# AMR3350_old.net
KiCad netlist of a schematic drawn in EAGLE
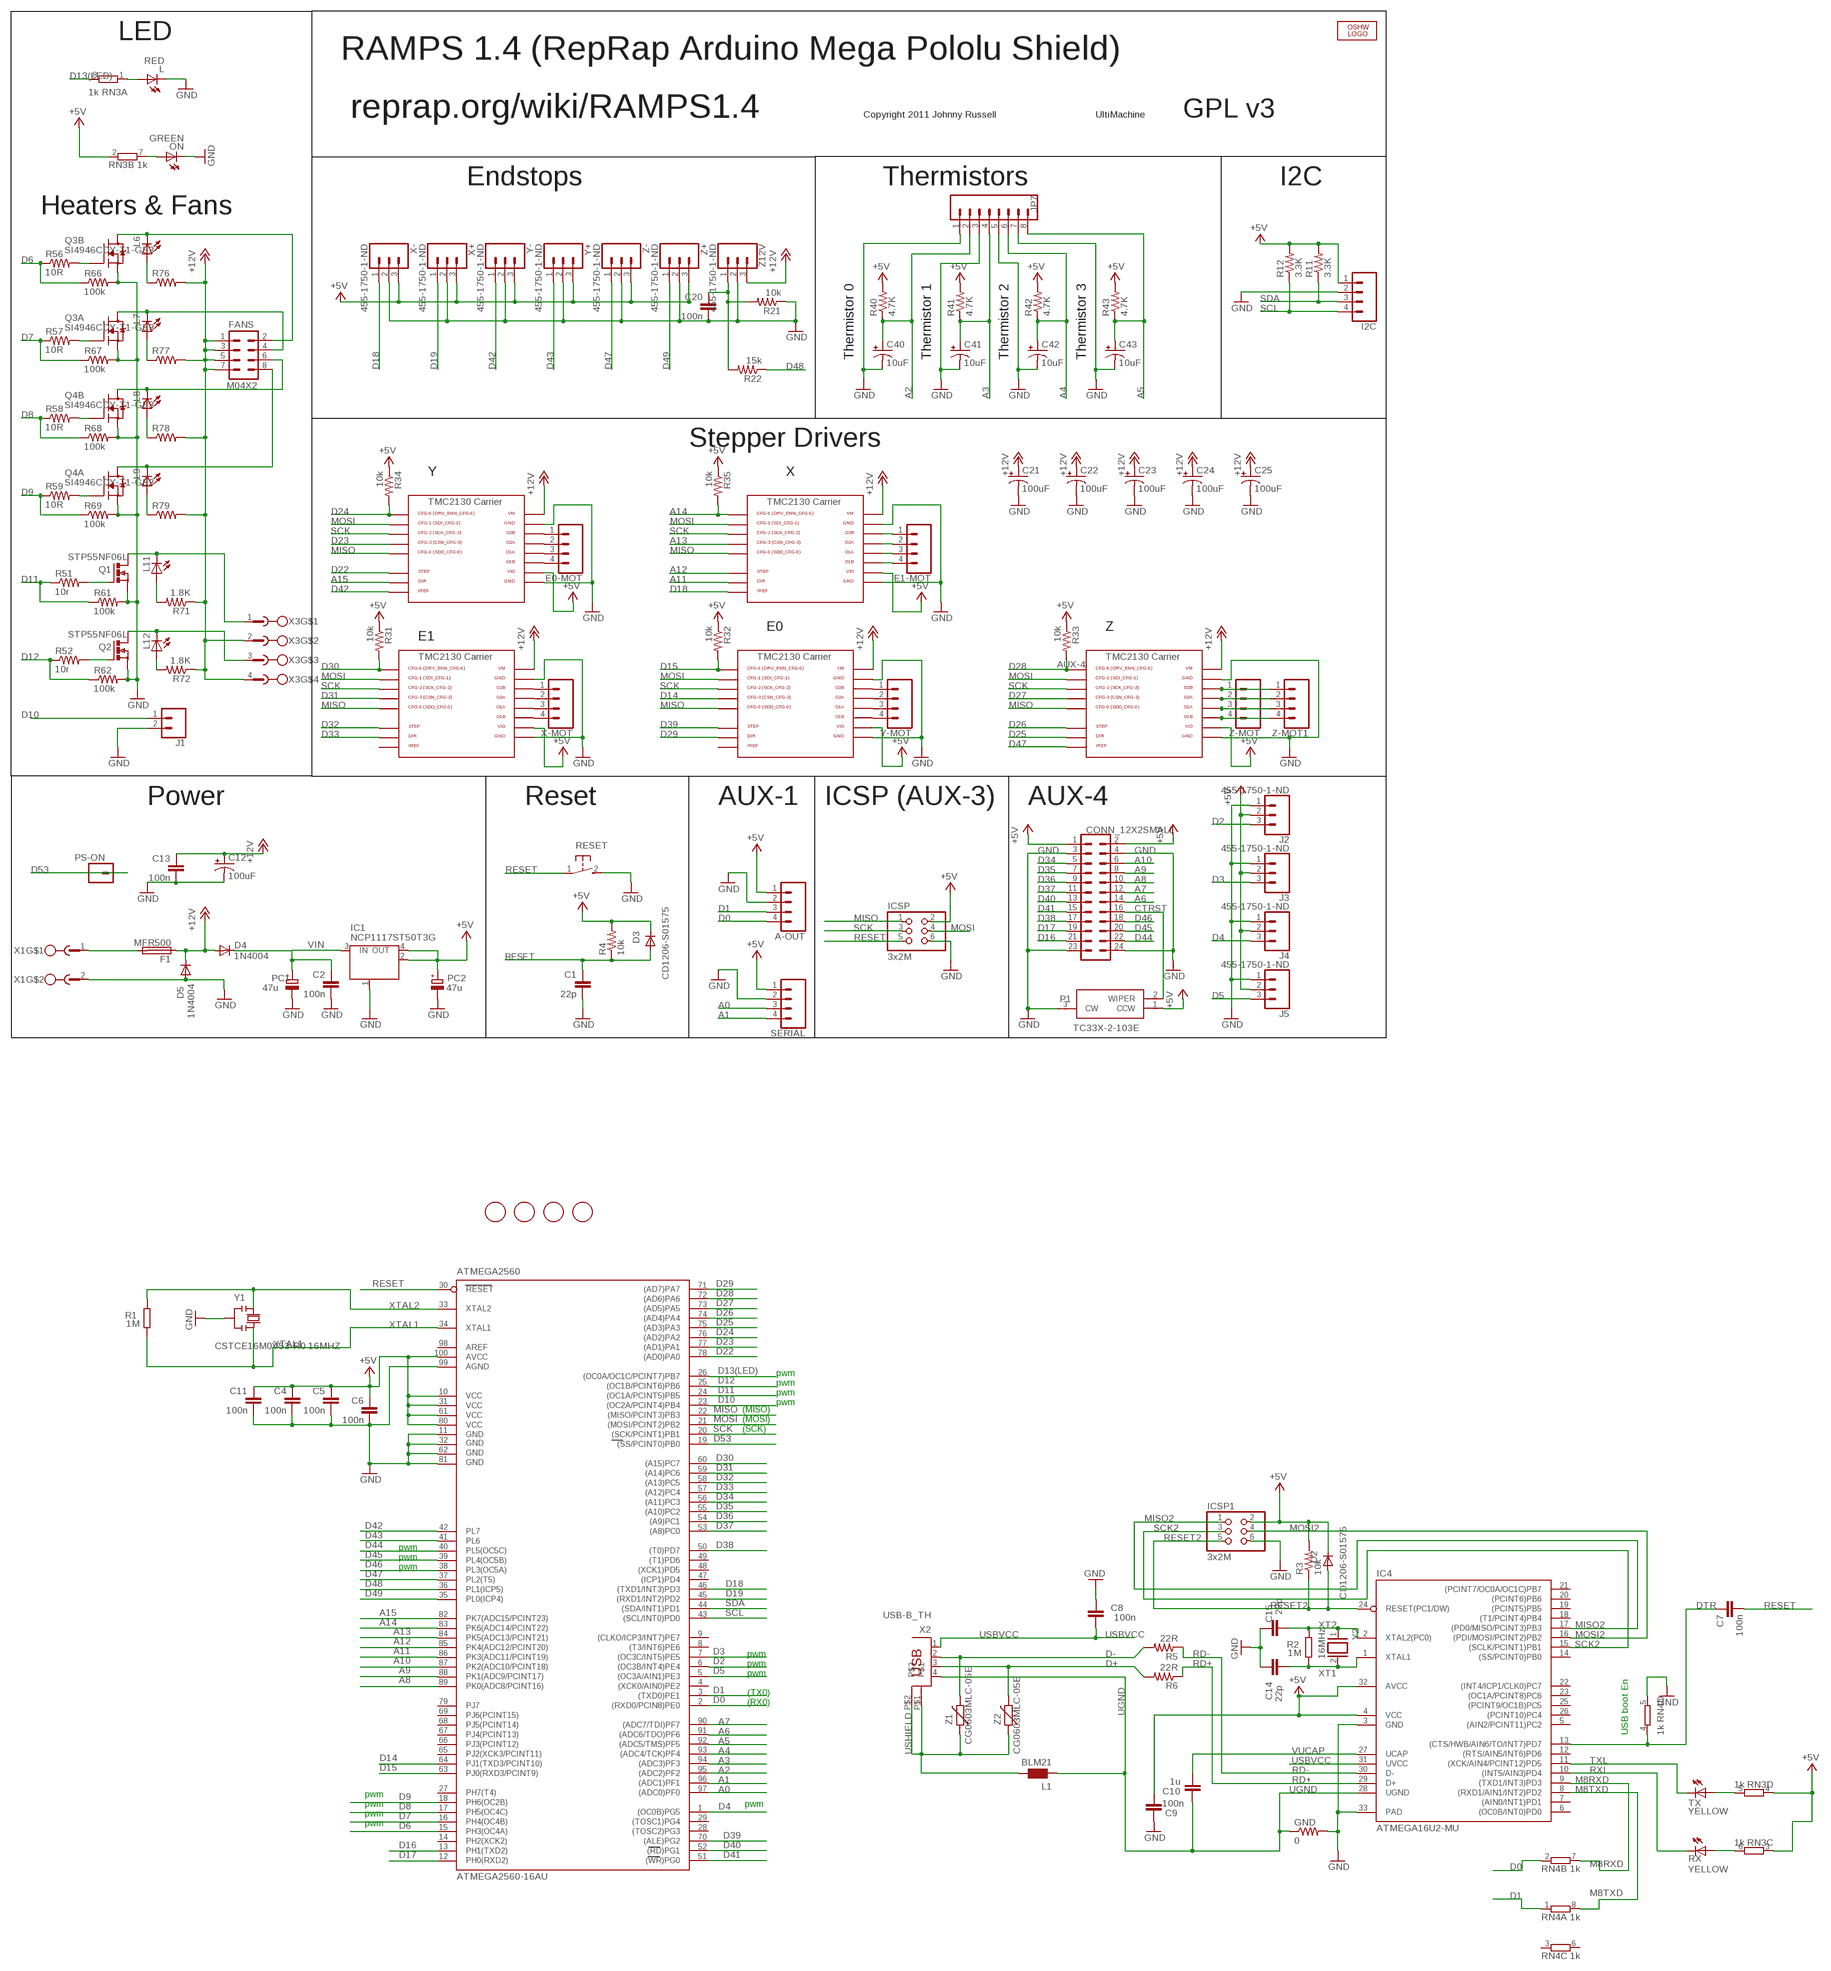
[diagram p0: schematic, sheet 1]

(export (version "E")
  (design (tool "Eeschema 10.0.6"))
  (components
    (comp (ref "A-OUT")
      (value "CONN_04SMALL")
      (footprint "eagle-import:1X04_SMALL")
      (libsource (lib "eagle-import") (part "CONN_04SMALL"))
    )
    (comp (ref "ATMEGA2560")
      (value "ATMEGA2560-16AU")
      (footprint "eagle-import:TQFP100")
      (libsource (lib "eagle-import") (part "ATMEGA2560AU2560-16"))
    )
    (comp (ref "AUX-4")
      (value "CONN_12X2SMALL")
      (footprint "eagle-import:2X12_SMALL")
      (libsource (lib "eagle-import") (part "CONN_12X2SMALL"))
    )
    (comp (ref "C1")
      (value "22p")
      (footprint "eagle-import:C0805RND")
      (libsource (lib "eagle-import") (part "C-EU"))
    )
    (comp (ref "C2")
      (value "100n")
      (footprint "eagle-import:C0805RND")
      (libsource (lib "eagle-import") (part "C-EU"))
    )
    (comp (ref "C4")
      (value "100n")
      (footprint "eagle-import:C0805RND")
      (libsource (lib "eagle-import") (part "C-EU"))
    )
    (comp (ref "C5")
      (value "100n")
      (footprint "eagle-import:C0805RND")
      (libsource (lib "eagle-import") (part "C-EU"))
    )
    (comp (ref "C6")
      (value "100n")
      (footprint "eagle-import:C0805RND")
      (libsource (lib "eagle-import") (part "C-EU"))
    )
    (comp (ref "C7")
      (value "100n")
      (footprint "eagle-import:C0805RND")
      (libsource (lib "eagle-import") (part "C-EU"))
    )
    (comp (ref "C8")
      (value "100n")
      (footprint "eagle-import:C0603-ROUND")
      (libsource (lib "eagle-import") (part "C-EU0603-RND"))
    )
    (comp (ref "C9")
      (value "100n")
      (footprint "eagle-import:C0603-ROUND")
      (libsource (lib "eagle-import") (part "C-EU0603-RND"))
    )
    (comp (ref "C10")
      (value "1u")
      (footprint "eagle-import:C0603-ROUND")
      (libsource (lib "eagle-import") (part "C-EU0603-RND"))
    )
    (comp (ref "C11")
      (value "100n")
      (footprint "eagle-import:C0603-ROUND")
      (libsource (lib "eagle-import") (part "C-EU0603-RND"))
    )
    (comp (ref "C12")
      (value "100uF")
      (footprint "eagle-import:153CLV-0605")
      (libsource (lib "eagle-import") (part "CPOL-US153CLV-0605"))
    )
    (comp (ref "C13")
      (value "100n")
      (footprint "eagle-import:C0805RND")
      (libsource (lib "eagle-import") (part "C-EU"))
    )
    (comp (ref "C14")
      (value "22p")
      (footprint "eagle-import:C0603-ROUND")
      (libsource (lib "eagle-import") (part "C-EU0603-RND"))
    )
    (comp (ref "C15")
      (value "22p")
      (footprint "eagle-import:C0603-ROUND")
      (libsource (lib "eagle-import") (part "C-EU0603-RND"))
    )
    (comp (ref "C20")
      (value "100n")
      (footprint "eagle-import:C0805RND")
      (libsource (lib "eagle-import") (part "C-EU"))
    )
    (comp (ref "C21")
      (value "100uF")
      (footprint "eagle-import:153CLV-0605")
      (libsource (lib "eagle-import") (part "CPOL-US153CLV-0605"))
    )
    (comp (ref "C22")
      (value "100uF")
      (footprint "eagle-import:153CLV-0605")
      (libsource (lib "eagle-import") (part "CPOL-US153CLV-0605"))
    )
    (comp (ref "C23")
      (value "100uF")
      (footprint "eagle-import:153CLV-0605")
      (libsource (lib "eagle-import") (part "CPOL-US153CLV-0605"))
    )
    (comp (ref "C24")
      (value "100uF")
      (footprint "eagle-import:153CLV-0605")
      (libsource (lib "eagle-import") (part "CPOL-US153CLV-0605"))
    )
    (comp (ref "C25")
      (value "100uF")
      (footprint "eagle-import:153CLV-0605")
      (libsource (lib "eagle-import") (part "CPOL-US153CLV-0605"))
    )
    (comp (ref "C40")
      (value "10uF")
      (footprint "eagle-import:153CLV-0405")
      (libsource (lib "eagle-import") (part "CPOL-US153CLV-0405"))
    )
    (comp (ref "C41")
      (value "10uF")
      (footprint "eagle-import:153CLV-0405")
      (libsource (lib "eagle-import") (part "CPOL-US153CLV-0405"))
    )
    (comp (ref "C42")
      (value "10uF")
      (footprint "eagle-import:153CLV-0405")
      (libsource (lib "eagle-import") (part "CPOL-US153CLV-0405"))
    )
    (comp (ref "C43")
      (value "10uF")
      (footprint "eagle-import:153CLV-0405")
      (libsource (lib "eagle-import") (part "CPOL-US153CLV-0405"))
    )
    (comp (ref "D2")
      (value "CD1206-S01575")
      (footprint "eagle-import:MINIMELF")
      (libsource (lib "eagle-import") (part "DIODE-MINIMELF"))
    )
    (comp (ref "D3")
      (value "CD1206-S01575")
      (footprint "eagle-import:MINIMELF")
      (libsource (lib "eagle-import") (part "DIODE-MINIMELF"))
    )
    (comp (ref "D4")
      (value "1N4004")
      (footprint "eagle-import:DO41-10")
      (libsource (lib "eagle-import") (part "1N4004"))
    )
    (comp (ref "D5")
      (value "1N4004")
      (footprint "eagle-import:DO41-10")
      (libsource (lib "eagle-import") (part "1N4004"))
    )
    (comp (ref "E0-MOT")
      (value "CONN_04SMALL")
      (footprint "eagle-import:1X04_SMALL")
      (libsource (lib "eagle-import") (part "CONN_04SMALL"))
    )
    (comp (ref "E1-MOT")
      (value "CONN_04SMALL")
      (footprint "eagle-import:1X04_SMALL")
      (libsource (lib "eagle-import") (part "CONN_04SMALL"))
    )
    (comp (ref "F1")
      (value "MFR500")
      (footprint "eagle-import:MFR500")
      (libsource (lib "eagle-import") (part "PTCFUSE"))
    )
    (comp (ref "FANS")
      (value "M04X2")
      (footprint "eagle-import:2X4")
      (libsource (lib "eagle-import") (part "M04X2"))
    )
    (comp (ref "FD1")
      (value "FIDUCIALMOUNT")
      (footprint "eagle-import:FIDUCIA-MOUNT")
      (libsource (lib "eagle-import") (part "FIDUCIALMOUNT"))
    )
    (comp (ref "FD2")
      (value "FIDUCIALMOUNT")
      (footprint "eagle-import:FIDUCIA-MOUNT")
      (libsource (lib "eagle-import") (part "FIDUCIALMOUNT"))
    )
    (comp (ref "FD3")
      (value "FIDUCIALMOUNT")
      (footprint "eagle-import:FIDUCIA-MOUNT")
      (libsource (lib "eagle-import") (part "FIDUCIALMOUNT"))
    )
    (comp (ref "FD4")
      (value "FIDUCIALMOUNT")
      (footprint "eagle-import:FIDUCIA-MOUNT")
      (libsource (lib "eagle-import") (part "FIDUCIALMOUNT"))
    )
    (comp (ref "GND")
      (value "0")
      (footprint "eagle-import:R0201")
      (libsource (lib "eagle-import") (part "R-US_R0201"))
    )
    (comp (ref "I2C")
      (value "CONN_04SMALL")
      (footprint "eagle-import:1X04_SMALL")
      (libsource (lib "eagle-import") (part "CONN_04SMALL"))
    )
    (comp (ref "IC1")
      (value "NCP1117ST50T3G")
      (footprint "eagle-import:SOT223")
      (libsource (lib "eagle-import") (part "MC33269ST-3.3T3"))
    )
    (comp (ref "IC4")
      (value "ATMEGA16U2-MU")
      (footprint "eagle-import:MLF32")
      (libsource (lib "eagle-import") (part "ATMEGA16U2-MU"))
    )
    (comp (ref "ICSP")
      (value "3x2M")
      (footprint "eagle-import:2X03")
      (libsource (lib "eagle-import") (part "PINHD-2X3"))
    )
    (comp (ref "ICSP1")
      (value "3x2M")
      (footprint "eagle-import:2X03")
      (libsource (lib "eagle-import") (part "PINHD-2X3"))
    )
    (comp (ref "J1")
      (value "CONN_02")
      (footprint "eagle-import:1X02")
      (libsource (lib "eagle-import") (part "CONN_02"))
    )
    (comp (ref "J2")
      (value "455-1750-1-ND")
      (footprint "eagle-import:1X03_SMALL")
      (libsource (lib "eagle-import") (part "CONN_03SMALL"))
    )
    (comp (ref "J3")
      (value "455-1750-1-ND")
      (footprint "eagle-import:1X03_SMALL")
      (libsource (lib "eagle-import") (part "CONN_03SMALL"))
    )
    (comp (ref "J4")
      (value "455-1750-1-ND")
      (footprint "eagle-import:1X03_SMALL")
      (libsource (lib "eagle-import") (part "CONN_03SMALL"))
    )
    (comp (ref "J5")
      (value "455-1750-1-ND")
      (footprint "eagle-import:1X03_SMALL")
      (libsource (lib "eagle-import") (part "CONN_03SMALL"))
    )
    (comp (ref "JP7")
      (value "CONN_08")
      (footprint "eagle-import:1X08_SMALL")
      (libsource (lib "eagle-import") (part "CONN_08"))
    )
    (comp (ref "L")
      (value "RED")
      (footprint "eagle-import:CHIP-LED0805")
      (libsource (lib "eagle-import") (part "LEDCHIP-LED0805"))
    )
    (comp (ref "L1")
      (value "BLM21")
      (footprint "eagle-import:0805")
      (libsource (lib "eagle-import") (part "WE-CBF_0805"))
    )
    (comp (ref "L6")
      (value "LEDCHIP-LED0603")
      (footprint "eagle-import:CHIP-LED0603")
      (libsource (lib "eagle-import") (part "LEDCHIP-LED0603"))
    )
    (comp (ref "L7")
      (value "LEDCHIP-LED0603")
      (footprint "eagle-import:CHIP-LED0603")
      (libsource (lib "eagle-import") (part "LEDCHIP-LED0603"))
    )
    (comp (ref "L8")
      (value "LEDCHIP-LED0603")
      (footprint "eagle-import:CHIP-LED0603")
      (libsource (lib "eagle-import") (part "LEDCHIP-LED0603"))
    )
    (comp (ref "L9")
      (value "LEDCHIP-LED0603")
      (footprint "eagle-import:CHIP-LED0603")
      (libsource (lib "eagle-import") (part "LEDCHIP-LED0603"))
    )
    (comp (ref "L11")
      (value "LEDCHIP-LED0805")
      (footprint "eagle-import:CHIP-LED0805")
      (libsource (lib "eagle-import") (part "LEDCHIP-LED0805"))
    )
    (comp (ref "L12")
      (value "LEDCHIP-LED0805")
      (footprint "eagle-import:CHIP-LED0805")
      (libsource (lib "eagle-import") (part "LEDCHIP-LED0805"))
    )
    (comp (ref "LOGO2")
      (value "OSHW_LOGO_6MILX0100-NT")
      (footprint "eagle-import:OSHW_6X100_NOTEXT")
      (libsource (lib "eagle-import") (part "OSHW_LOGO_6MILX0100-NT"))
    )
    (comp (ref "ON")
      (value "GREEN")
      (footprint "eagle-import:CHIP-LED0805")
      (libsource (lib "eagle-import") (part "LEDCHIP-LED0805"))
    )
    (comp (ref "P1")
      (value "TC33X-2-103E")
      (footprint "eagle-import:TC33X-2_1")
      (fields (field (name "RS_PART_NUMBER") "1673549"))
      (libsource (lib "eagle-import") (part "TC33X-2-103E"))
    )
    (comp (ref "PC1")
      (value "47u")
      (footprint "eagle-import:PANASONIC_D")
      (libsource (lib "eagle-import") (part "CPOL-EUD"))
    )
    (comp (ref "PC2")
      (value "47u")
      (footprint "eagle-import:PANASONIC_D")
      (libsource (lib "eagle-import") (part "CPOL-EUD"))
    )
    (comp (ref "PS-ON")
      (value "CONN_01SMALL")
      (footprint "eagle-import:1X01_SMALL")
      (libsource (lib "eagle-import") (part "CONN_01SMALL"))
    )
    (comp (ref "Q1")
      (value "STP55NF06L")
      (footprint "eagle-import:TO220BV")
      (libsource (lib "eagle-import") (part "IRF512"))
    )
    (comp (ref "Q2")
      (value "STP55NF06L")
      (footprint "eagle-import:TO220BV")
      (libsource (lib "eagle-import") (part "IRF512"))
    )
    (comp (ref "Q3")
      (value "SI4946CDY-T1-GE3")
      (footprint "eagle-import:SOIC127P600X175-8N")
      (libsource (lib "eagle-import") (part "SI4946CDY-T1-GE3"))
    )
    (comp (ref "Q4")
      (value "SI4946CDY-T1-GE3")
      (footprint "eagle-import:SOIC127P600X175-8N")
      (libsource (lib "eagle-import") (part "SI4946CDY-T1-GE3"))
    )
    (comp (ref "R1")
      (value "1M")
      (footprint "eagle-import:R0805RND")
      (libsource (lib "eagle-import") (part "R-EU_"))
    )
    (comp (ref "R2")
      (value "1M")
      (footprint "eagle-import:R0603-ROUND")
      (libsource (lib "eagle-import") (part "R-EU_R0603"))
    )
    (comp (ref "R3")
      (value "10k")
      (footprint "eagle-import:R0805")
      (libsource (lib "eagle-import") (part "resistor_348_R-US_R0805"))
    )
    (comp (ref "R4")
      (value "10k")
      (footprint "eagle-import:R0805")
      (libsource (lib "eagle-import") (part "resistor_348_R-US_R0805"))
    )
    (comp (ref "R5")
      (value "22R")
      (footprint "eagle-import:R0603")
      (libsource (lib "eagle-import") (part "resistor_348_R-US_R0603"))
    )
    (comp (ref "R6")
      (value "22R")
      (footprint "eagle-import:R0603")
      (libsource (lib "eagle-import") (part "resistor_348_R-US_R0603"))
    )
    (comp (ref "R11")
      (value "3.3K")
      (footprint "eagle-import:R0805")
      (libsource (lib "eagle-import") (part "R-US_R0805"))
    )
    (comp (ref "R12")
      (value "3.3K")
      (footprint "eagle-import:R0805")
      (libsource (lib "eagle-import") (part "R-US_R0805"))
    )
    (comp (ref "R21")
      (value "10k")
      (footprint "eagle-import:R0805")
      (libsource (lib "eagle-import") (part "R-US_R0805"))
    )
    (comp (ref "R22")
      (value "15k")
      (footprint "eagle-import:R0805")
      (libsource (lib "eagle-import") (part "R-US_R0805"))
    )
    (comp (ref "R31")
      (value "10k")
      (footprint "eagle-import:R0805")
      (libsource (lib "eagle-import") (part "R-US_R0805"))
    )
    (comp (ref "R32")
      (value "10k")
      (footprint "eagle-import:R0805")
      (libsource (lib "eagle-import") (part "R-US_R0805"))
    )
    (comp (ref "R33")
      (value "10k")
      (footprint "eagle-import:R0805")
      (libsource (lib "eagle-import") (part "R-US_R0805"))
    )
    (comp (ref "R34")
      (value "10k")
      (footprint "eagle-import:R0805")
      (libsource (lib "eagle-import") (part "R-US_R0805"))
    )
    (comp (ref "R35")
      (value "10k")
      (footprint "eagle-import:R0805")
      (libsource (lib "eagle-import") (part "R-US_R0805"))
    )
    (comp (ref "R40")
      (value "4.7K")
      (footprint "eagle-import:R0805")
      (libsource (lib "eagle-import") (part "R-US_R0805"))
    )
    (comp (ref "R41")
      (value "4.7K")
      (footprint "eagle-import:R0805")
      (libsource (lib "eagle-import") (part "R-US_R0805"))
    )
    (comp (ref "R42")
      (value "4.7K")
      (footprint "eagle-import:R0805")
      (libsource (lib "eagle-import") (part "R-US_R0805"))
    )
    (comp (ref "R43")
      (value "4.7K")
      (footprint "eagle-import:R0805")
      (libsource (lib "eagle-import") (part "R-US_R0805"))
    )
    (comp (ref "R51")
      (value "10r")
      (footprint "eagle-import:R0805")
      (libsource (lib "eagle-import") (part "resistor_R-US_R0805"))
    )
    (comp (ref "R52")
      (value "10r")
      (footprint "eagle-import:M0805")
      (libsource (lib "eagle-import") (part "resistor_R-US_M0805"))
    )
    (comp (ref "R56")
      (value "10R")
      (footprint "eagle-import:R0805")
      (libsource (lib "eagle-import") (part "resistor_348_R-US_R0805"))
    )
    (comp (ref "R57")
      (value "10R")
      (footprint "eagle-import:R0805")
      (libsource (lib "eagle-import") (part "resistor_348_R-US_R0805"))
    )
    (comp (ref "R58")
      (value "10R")
      (footprint "eagle-import:R0805")
      (libsource (lib "eagle-import") (part "resistor_348_R-US_R0805"))
    )
    (comp (ref "R59")
      (value "10R")
      (footprint "eagle-import:R0805")
      (libsource (lib "eagle-import") (part "resistor_348_R-US_R0805"))
    )
    (comp (ref "R61")
      (value "100k")
      (footprint "eagle-import:R0805")
      (libsource (lib "eagle-import") (part "R-US_R0805"))
    )
    (comp (ref "R62")
      (value "100k")
      (footprint "eagle-import:R0805")
      (libsource (lib "eagle-import") (part "R-US_R0805"))
    )
    (comp (ref "R66")
      (value "100k")
      (footprint "eagle-import:R0805")
      (libsource (lib "eagle-import") (part "resistor_348_R-US_R0805"))
    )
    (comp (ref "R67")
      (value "100k")
      (footprint "eagle-import:R0805")
      (libsource (lib "eagle-import") (part "resistor_348_R-US_R0805"))
    )
    (comp (ref "R68")
      (value "100k")
      (footprint "eagle-import:R0805")
      (libsource (lib "eagle-import") (part "resistor_348_R-US_R0805"))
    )
    (comp (ref "R69")
      (value "100k")
      (footprint "eagle-import:R0805")
      (libsource (lib "eagle-import") (part "resistor_348_R-US_R0805"))
    )
    (comp (ref "R71")
      (value "1.8K")
      (footprint "eagle-import:R0805")
      (libsource (lib "eagle-import") (part "R-US_R0805"))
    )
    (comp (ref "R72")
      (value "1.8K")
      (footprint "eagle-import:R0805")
      (libsource (lib "eagle-import") (part "R-US_R0805"))
    )
    (comp (ref "R76")
      (value "R-US_R0603")
      (footprint "eagle-import:R0603")
      (libsource (lib "eagle-import") (part "resistor_348_R-US_R0603"))
    )
    (comp (ref "R77")
      (value "R-US_R0603")
      (footprint "eagle-import:R0603")
      (libsource (lib "eagle-import") (part "resistor_348_R-US_R0603"))
    )
    (comp (ref "R78")
      (value "R-US_R0603")
      (footprint "eagle-import:R0603")
      (libsource (lib "eagle-import") (part "resistor_348_R-US_R0603"))
    )
    (comp (ref "R79")
      (value "R-US_R0603")
      (footprint "eagle-import:R0603")
      (libsource (lib "eagle-import") (part "resistor_348_R-US_R0603"))
    )
    (comp (ref "RESET")
      (value "31-XX")
      (footprint "eagle-import:B3F-31XX")
      (fields (field (name "MPN") "B3F-3100"))
      (libsource (lib "eagle-import") (part "31-XX"))
    )
    (comp (ref "RN3")
      (value "1k")
      (footprint "eagle-import:CAY16")
      (libsource (lib "eagle-import") (part "4R-NCAY16"))
    )
    (comp (ref "RN4")
      (value "1k")
      (footprint "eagle-import:CAY16")
      (libsource (lib "eagle-import") (part "4R-NCAY16"))
    )
    (comp (ref "RX")
      (value "YELLOW")
      (footprint "eagle-import:CHIP-LED0805")
      (libsource (lib "eagle-import") (part "LEDCHIP-LED0805"))
    )
    (comp (ref "SERIAL")
      (value "CONN_04SMALL")
      (footprint "eagle-import:1X04_SMALL")
      (libsource (lib "eagle-import") (part "CONN_04SMALL"))
    )
    (comp (ref "TX")
      (value "YELLOW")
      (footprint "eagle-import:CHIP-LED0805")
      (libsource (lib "eagle-import") (part "LEDCHIP-LED0805"))
    )
    (comp (ref "U$1")
      (value "TMC2130BREAKOUT")
      (footprint "eagle-import:TMC2130BREAKOUT")
      (libsource (lib "eagle-import") (part "TMC2130BREAKOUT"))
    )
    (comp (ref "U$2")
      (value "TMC2130BREAKOUT")
      (footprint "eagle-import:TMC2130BREAKOUT")
      (libsource (lib "eagle-import") (part "TMC2130BREAKOUT"))
    )
    (comp (ref "U$3")
      (value "TMC2130BREAKOUT")
      (footprint "eagle-import:TMC2130BREAKOUT")
      (libsource (lib "eagle-import") (part "TMC2130BREAKOUT"))
    )
    (comp (ref "U$4")
      (value "TMC2130BREAKOUT")
      (footprint "eagle-import:TMC2130BREAKOUT")
      (libsource (lib "eagle-import") (part "TMC2130BREAKOUT"))
    )
    (comp (ref "U$5")
      (value "TMC2130BREAKOUT")
      (footprint "eagle-import:TMC2130BREAKOUT")
      (libsource (lib "eagle-import") (part "TMC2130BREAKOUT"))
    )
    (comp (ref "X+")
      (value "455-1750-1-ND")
      (footprint "eagle-import:1X03_SMALL")
      (libsource (lib "eagle-import") (part "CONN_03SMALL"))
    )
    (comp (ref "X-")
      (value "455-1750-1-ND")
      (footprint "eagle-import:1X03_SMALL")
      (libsource (lib "eagle-import") (part "CONN_03SMALL"))
    )
    (comp (ref "X-MOT")
      (value "CONN_04SMALL")
      (footprint "eagle-import:1X04_SMALL")
      (libsource (lib "eagle-import") (part "CONN_04SMALL"))
    )
    (comp (ref "X1")
      (value "2-PIN")
      (footprint "eagle-import:2-PIN")
      (libsource (lib "eagle-import") (part "2-PIN"))
    )
    (comp (ref "X2")
      (value "USB-B_TH")
      (footprint "eagle-import:PN61729-NOSILK")
      (libsource (lib "eagle-import") (part "PN61729NOSILK"))
    )
    (comp (ref "X3")
      (value "4-PIN")
      (footprint "eagle-import:4-PIN")
      (libsource (lib "eagle-import") (part "4-PIN"))
    )
    (comp (ref "Y+")
      (value "455-1750-1-ND")
      (footprint "eagle-import:1X03_SMALL")
      (libsource (lib "eagle-import") (part "CONN_03SMALL"))
    )
    (comp (ref "Y-")
      (value "455-1750-1-ND")
      (footprint "eagle-import:1X03_SMALL")
      (libsource (lib "eagle-import") (part "CONN_03SMALL"))
    )
    (comp (ref "Y-MOT")
      (value "CONN_04SMALL")
      (footprint "eagle-import:1X04_SMALL")
      (libsource (lib "eagle-import") (part "CONN_04SMALL"))
    )
    (comp (ref "Y1")
      (value "CSTCE16M0V53-R0 16MHZ")
      (footprint "eagle-import:RESONATOR")
      (libsource (lib "eagle-import") (part "RESONATORMU"))
    )
    (comp (ref "Y2")
      (value "16MHz")
      (footprint "eagle-import:QS")
      (libsource (lib "eagle-import") (part "XTAL/S"))
    )
    (comp (ref "Z+")
      (value "455-1750-1-ND")
      (footprint "eagle-import:1X03_SMALL")
      (libsource (lib "eagle-import") (part "CONN_03SMALL"))
    )
    (comp (ref "Z-")
      (value "455-1750-1-ND")
      (footprint "eagle-import:1X03_SMALL")
      (libsource (lib "eagle-import") (part "CONN_03SMALL"))
    )
    (comp (ref "Z-MOT")
      (value "CONN_04SMALL")
      (footprint "eagle-import:1X04_SMALL")
      (libsource (lib "eagle-import") (part "CONN_04SMALL"))
    )
    (comp (ref "Z-MOT1")
      (value "CONN_04SMALL")
      (footprint "eagle-import:1X04_SMALL")
      (libsource (lib "eagle-import") (part "CONN_04SMALL"))
    )
    (comp (ref "Z1")
      (value "CG0603MLC-05E")
      (footprint "eagle-import:CT_CN0603")
      (libsource (lib "eagle-import") (part "VARISTORCN0603"))
    )
    (comp (ref "Z2")
      (value "CG0603MLC-05E")
      (footprint "eagle-import:CT_CN0603")
      (libsource (lib "eagle-import") (part "VARISTORCN0603"))
    )
    (comp (ref "Z12V")
      (value "455-1750-1-ND")
      (footprint "eagle-import:1X03_SMALL")
      (libsource (lib "eagle-import") (part "CONN_03SMALL"))
    )
  )
  (nets
    (net (code "1") (name "+5V") (class "Default")
      (node (ref "A-OUT") (pin "1") (pinfunction "1_1") (pintype "passive"))
      (node (ref "ATMEGA2560") (pin "10") (pinfunction "VCC_10") (pintype "power_in"))
      (node (ref "ATMEGA2560") (pin "100") (pinfunction "AVCC_100") (pintype "power_in"))
      (node (ref "ATMEGA2560") (pin "31") (pinfunction "VCC1_31") (pintype "power_in"))
      (node (ref "ATMEGA2560") (pin "61") (pinfunction "VCC2_61") (pintype "power_in"))
      (node (ref "ATMEGA2560") (pin "80") (pinfunction "VCC3_80") (pintype "power_in"))
      (node (ref "AUX-4") (pin "1") (pinfunction "1_1") (pintype "passive"))
      (node (ref "AUX-4") (pin "2") (pinfunction "2_2") (pintype "passive"))
      (node (ref "C11") (pin "1") (pinfunction "1_1") (pintype "passive"))
      (node (ref "C4") (pin "1") (pinfunction "1_1") (pintype "passive"))
      (node (ref "C5") (pin "1") (pinfunction "1_1") (pintype "passive"))
      (node (ref "C6") (pin "1") (pinfunction "1_1") (pintype "passive"))
      (node (ref "C9") (pin "1") (pinfunction "1_1") (pintype "passive"))
      (node (ref "D2") (pin "C") (pinfunction "C_C") (pintype "passive"))
      (node (ref "D3") (pin "C") (pinfunction "C_C") (pintype "passive"))
      (node (ref "I2C") (pin "1") (pinfunction "1_1") (pintype "passive"))
      (node (ref "IC1") (pin "2") (pinfunction "OUT_2") (pintype "passive"))
      (node (ref "IC1") (pin "4") (pinfunction "OUT_4") (pintype "passive"))
      (node (ref "IC4") (pin "32") (pinfunction "AVCC_32") (pintype "power_in"))
      (node (ref "IC4") (pin "4") (pinfunction "VCC_4") (pintype "power_in"))
      (node (ref "ICSP") (pin "2") (pinfunction "2_2") (pintype "passive"))
      (node (ref "ICSP1") (pin "2") (pinfunction "2_2") (pintype "passive"))
      (node (ref "J2") (pin "2") (pinfunction "2_2") (pintype "passive"))
      (node (ref "J3") (pin "2") (pinfunction "2_2") (pintype "passive"))
      (node (ref "J4") (pin "2") (pinfunction "2_2") (pintype "passive"))
      (node (ref "J5") (pin "2") (pinfunction "2_2") (pintype "passive"))
      (node (ref "P1") (pin "1") (pinfunction "CCW_1") (pintype "bidirectional"))
      (node (ref "PC2") (pin "+") (pinfunction "+_+") (pintype "passive"))
      (node (ref "R11") (pin "2") (pinfunction "2_2") (pintype "passive"))
      (node (ref "R12") (pin "2") (pinfunction "2_2") (pintype "passive"))
      (node (ref "R3") (pin "2") (pinfunction "2_2") (pintype "passive"))
      (node (ref "R31") (pin "1") (pinfunction "1_1") (pintype "passive"))
      (node (ref "R32") (pin "1") (pinfunction "1_1") (pintype "passive"))
      (node (ref "R33") (pin "1") (pinfunction "1_1") (pintype "passive"))
      (node (ref "R34") (pin "1") (pinfunction "1_1") (pintype "passive"))
      (node (ref "R35") (pin "1") (pinfunction "1_1") (pintype "passive"))
      (node (ref "R4") (pin "2") (pinfunction "2_2") (pintype "passive"))
      (node (ref "R40") (pin "2") (pinfunction "2_2") (pintype "passive"))
      (node (ref "R41") (pin "2") (pinfunction "2_2") (pintype "passive"))
      (node (ref "R42") (pin "2") (pinfunction "2_2") (pintype "passive"))
      (node (ref "R43") (pin "2") (pinfunction "2_2") (pintype "passive"))
      (node (ref "RN3") (pin "2") (pinfunction "1_2") (pintype "passive"))
      (node (ref "RN3") (pin "3") (pinfunction "1_3") (pintype "passive"))
      (node (ref "RN3") (pin "4") (pinfunction "1_4") (pintype "passive"))
      (node (ref "SERIAL") (pin "1") (pinfunction "1_1") (pintype "passive"))
      (node (ref "U$1") (pin "VIO") (pinfunction "VIO_VIO") (pintype "power_in"))
      (node (ref "U$2") (pin "VIO") (pinfunction "VIO_VIO") (pintype "power_in"))
      (node (ref "U$3") (pin "VIO") (pinfunction "VIO_VIO") (pintype "power_in"))
      (node (ref "U$4") (pin "VIO") (pinfunction "VIO_VIO") (pintype "power_in"))
      (node (ref "U$5") (pin "VIO") (pinfunction "VIO_VIO") (pintype "power_in"))
      (node (ref "X+") (pin "3") (pinfunction "3_3") (pintype "passive"))
      (node (ref "X-") (pin "3") (pinfunction "3_3") (pintype "passive"))
      (node (ref "Y+") (pin "3") (pinfunction "3_3") (pintype "passive"))
      (node (ref "Y-") (pin "3") (pinfunction "3_3") (pintype "passive"))
      (node (ref "Z+") (pin "3") (pinfunction "3_3") (pintype "passive"))
      (node (ref "Z-") (pin "3") (pinfunction "3_3") (pintype "passive"))
    )
    (net (code "2") (name "+12V") (class "Default")
      (node (ref "C12") (pin "+") (pinfunction "+_+") (pintype "passive"))
      (node (ref "C13") (pin "1") (pinfunction "1_1") (pintype "passive"))
      (node (ref "C21") (pin "+") (pinfunction "+_+") (pintype "passive"))
      (node (ref "C22") (pin "+") (pinfunction "+_+") (pintype "passive"))
      (node (ref "C23") (pin "+") (pinfunction "+_+") (pintype "passive"))
      (node (ref "C24") (pin "+") (pinfunction "+_+") (pintype "passive"))
      (node (ref "C25") (pin "+") (pinfunction "+_+") (pintype "passive"))
      (node (ref "D4") (pin "A") (pinfunction "A_A") (pintype "passive"))
      (node (ref "D5") (pin "C") (pinfunction "C_C") (pintype "passive"))
      (node (ref "F1") (pin "1") (pinfunction "1_1") (pintype "passive"))
      (node (ref "FANS") (pin "1") (pinfunction "1_1") (pintype "passive"))
      (node (ref "FANS") (pin "3") (pinfunction "3_3") (pintype "passive"))
      (node (ref "FANS") (pin "5") (pinfunction "5_5") (pintype "passive"))
      (node (ref "FANS") (pin "7") (pinfunction "7_7") (pintype "passive"))
      (node (ref "R71") (pin "1") (pinfunction "1_1") (pintype "passive"))
      (node (ref "R72") (pin "1") (pinfunction "1_1") (pintype "passive"))
      (node (ref "R76") (pin "2") (pinfunction "2_2") (pintype "passive"))
      (node (ref "R77") (pin "2") (pinfunction "2_2") (pintype "passive"))
      (node (ref "R78") (pin "2") (pinfunction "2_2") (pintype "passive"))
      (node (ref "R79") (pin "2") (pinfunction "2_2") (pintype "passive"))
      (node (ref "U$1") (pin "VM") (pinfunction "VM_VM") (pintype "power_in"))
      (node (ref "U$2") (pin "VM") (pinfunction "VM_VM") (pintype "power_in"))
      (node (ref "U$3") (pin "VM") (pinfunction "VM_VM") (pintype "power_in"))
      (node (ref "U$4") (pin "VM") (pinfunction "VM_VM") (pintype "power_in"))
      (node (ref "U$5") (pin "VM") (pinfunction "VM_VM") (pintype "power_in"))
      (node (ref "X3") (pin "2") (pinfunction "1_2") (pintype "passive"))
      (node (ref "X3") (pin "4") (pinfunction "1_4") (pintype "passive"))
      (node (ref "Z12V") (pin "3") (pinfunction "3_3") (pintype "passive"))
    )
    (net (code "3") (name "/A0") (class "Default")
      (node (ref "ATMEGA2560") (pin "97") (pinfunction "(ADC0)PF0_97") (pintype "bidirectional"))
      (node (ref "SERIAL") (pin "3") (pinfunction "3_3") (pintype "passive"))
    )
    (net (code "4") (name "/A1") (class "Default")
      (node (ref "ATMEGA2560") (pin "96") (pinfunction "(ADC1)PF1_96") (pintype "bidirectional"))
      (node (ref "SERIAL") (pin "4") (pinfunction "4_4") (pintype "passive"))
    )
    (net (code "5") (name "/A2") (class "Default")
      (node (ref "ATMEGA2560") (pin "95") (pinfunction "(ADC2)PF2_95") (pintype "bidirectional"))
      (node (ref "C40") (pin "+") (pinfunction "+_+") (pintype "passive"))
      (node (ref "JP7") (pin "2") (pinfunction "2_2") (pintype "passive"))
      (node (ref "R40") (pin "1") (pinfunction "1_1") (pintype "passive"))
    )
    (net (code "6") (name "/A3") (class "Default")
      (node (ref "ATMEGA2560") (pin "94") (pinfunction "(ADC3)PF3_94") (pintype "bidirectional"))
      (node (ref "C41") (pin "+") (pinfunction "+_+") (pintype "passive"))
      (node (ref "JP7") (pin "4") (pinfunction "4_4") (pintype "passive"))
      (node (ref "R41") (pin "1") (pinfunction "1_1") (pintype "passive"))
    )
    (net (code "7") (name "/A4") (class "Default")
      (node (ref "ATMEGA2560") (pin "93") (pinfunction "(ADC4/TCK)PF4_93") (pintype "bidirectional"))
      (node (ref "C42") (pin "+") (pinfunction "+_+") (pintype "passive"))
      (node (ref "JP7") (pin "6") (pinfunction "6_6") (pintype "passive"))
      (node (ref "R42") (pin "1") (pinfunction "1_1") (pintype "passive"))
    )
    (net (code "8") (name "/A5") (class "Default")
      (node (ref "ATMEGA2560") (pin "92") (pinfunction "(ADC5/TMS)PF5_92") (pintype "bidirectional"))
      (node (ref "C43") (pin "+") (pinfunction "+_+") (pintype "passive"))
      (node (ref "JP7") (pin "8") (pinfunction "8_8") (pintype "passive"))
      (node (ref "R43") (pin "1") (pinfunction "1_1") (pintype "passive"))
    )
    (net (code "9") (name "/A6") (class "Default")
      (node (ref "ATMEGA2560") (pin "91") (pinfunction "(ADC6/TDO)PF6_91") (pintype "bidirectional"))
      (node (ref "AUX-4") (pin "14") (pinfunction "14_14") (pintype "passive"))
    )
    (net (code "10") (name "/A7") (class "Default")
      (node (ref "ATMEGA2560") (pin "90") (pinfunction "(ADC7/TDI)PF7_90") (pintype "bidirectional"))
      (node (ref "AUX-4") (pin "12") (pinfunction "12_12") (pintype "passive"))
    )
    (net (code "11") (name "/A8") (class "Default")
      (node (ref "ATMEGA2560") (pin "89") (pinfunction "PK0(ADC8/PCINT16)_89") (pintype "bidirectional"))
      (node (ref "AUX-4") (pin "10") (pinfunction "10_10") (pintype "passive"))
    )
    (net (code "12") (name "/A9") (class "Default")
      (node (ref "ATMEGA2560") (pin "88") (pinfunction "PK1(ADC9/PCINT17)_88") (pintype "bidirectional"))
      (node (ref "AUX-4") (pin "8") (pinfunction "8_8") (pintype "passive"))
    )
    (net (code "13") (name "/A10") (class "Default")
      (node (ref "ATMEGA2560") (pin "87") (pinfunction "PK2(ADC10/PCINT18)_87") (pintype "bidirectional"))
      (node (ref "AUX-4") (pin "6") (pinfunction "6_6") (pintype "passive"))
    )
    (net (code "14") (name "/A11") (class "Default")
      (node (ref "ATMEGA2560") (pin "86") (pinfunction "PK3(ADC11/PCINT19)_86") (pintype "bidirectional"))
      (node (ref "U$4") (pin "DIR") (pinfunction "DIR_DIR") (pintype "input"))
    )
    (net (code "15") (name "/A12") (class "Default")
      (node (ref "ATMEGA2560") (pin "85") (pinfunction "PK4(ADC12/PCINT20)_85") (pintype "bidirectional"))
      (node (ref "U$4") (pin "STEP") (pinfunction "STEP_STEP") (pintype "input"))
    )
    (net (code "16") (name "/A13") (class "Default")
      (node (ref "ATMEGA2560") (pin "84") (pinfunction "PK5(ADC13/PCINT21)_84") (pintype "bidirectional"))
      (node (ref "U$4") (pin "CFG-3") (pinfunction "CFG-3_CFG-3") (pintype "bidirectional"))
    )
    (net (code "17") (name "/A14") (class "Default")
      (node (ref "ATMEGA2560") (pin "83") (pinfunction "PK6(ADC14/PCINT22)_83") (pintype "bidirectional"))
      (node (ref "R35") (pin "2") (pinfunction "2_2") (pintype "passive"))
      (node (ref "U$4") (pin "CFG-6") (pinfunction "CFG-6_CFG-6") (pintype "bidirectional"))
    )
    (net (code "18") (name "/A15") (class "Default")
      (node (ref "ATMEGA2560") (pin "82") (pinfunction "PK7(ADC15/PCINT23)_82") (pintype "bidirectional"))
      (node (ref "U$5") (pin "DIR") (pinfunction "DIR_DIR") (pintype "input"))
    )
    (net (code "19") (name "/CTRST") (class "Default")
      (node (ref "AUX-4") (pin "16") (pinfunction "16_16") (pintype "passive"))
      (node (ref "P1") (pin "2") (pinfunction "WIPER_2") (pintype "bidirectional"))
    )
    (net (code "20") (name "/D+") (class "Default")
      (node (ref "R6") (pin "2") (pinfunction "2_2") (pintype "passive"))
      (node (ref "X2") (pin "3") (pinfunction "3_3") (pintype "bidirectional"))
      (node (ref "Z2") (pin "2") (pinfunction "2_2") (pintype "passive"))
    )
    (net (code "21") (name "/D-") (class "Default")
      (node (ref "R5") (pin "2") (pinfunction "2_2") (pintype "passive"))
      (node (ref "X2") (pin "2") (pinfunction "2_2") (pintype "bidirectional"))
      (node (ref "Z1") (pin "2") (pinfunction "2_2") (pintype "passive"))
    )
    (net (code "22") (name "/D0") (class "Default")
      (node (ref "A-OUT") (pin "4") (pinfunction "4_4") (pintype "passive"))
      (node (ref "ATMEGA2560") (pin "2") (pinfunction "(RXD0/PCIN8)PE0_2") (pintype "bidirectional"))
      (node (ref "RN4") (pin "2") (pinfunction "1_2") (pintype "passive"))
    )
    (net (code "23") (name "/D1") (class "Default")
      (node (ref "A-OUT") (pin "3") (pinfunction "3_3") (pintype "passive"))
      (node (ref "ATMEGA2560") (pin "3") (pinfunction "(TXD0)PE1_3") (pintype "bidirectional"))
      (node (ref "RN4") (pin "1") (pinfunction "1_1") (pintype "passive"))
    )
    (net (code "24") (name "/D2") (class "Default")
      (node (ref "ATMEGA2560") (pin "6") (pinfunction "(OC3B/INT4)PE4_6") (pintype "bidirectional"))
      (node (ref "J2") (pin "3") (pinfunction "3_3") (pintype "passive"))
    )
    (net (code "25") (name "/D3") (class "Default")
      (node (ref "ATMEGA2560") (pin "7") (pinfunction "(OC3C/INT5)PE5_7") (pintype "bidirectional"))
      (node (ref "J3") (pin "3") (pinfunction "3_3") (pintype "passive"))
    )
    (net (code "26") (name "/D4") (class "Default")
      (node (ref "ATMEGA2560") (pin "1") (pinfunction "(OC0B)PG5_1") (pintype "bidirectional"))
      (node (ref "J4") (pin "3") (pinfunction "3_3") (pintype "passive"))
    )
    (net (code "27") (name "/D5") (class "Default")
      (node (ref "ATMEGA2560") (pin "5") (pinfunction "(OC3A/AIN1)PE3_5") (pintype "bidirectional"))
      (node (ref "J5") (pin "3") (pinfunction "3_3") (pintype "passive"))
    )
    (net (code "28") (name "/D6") (class "Default")
      (node (ref "ATMEGA2560") (pin "15") (pinfunction "PH3(OC4A)_15") (pintype "bidirectional"))
      (node (ref "R56") (pin "1") (pinfunction "1_1") (pintype "passive"))
      (node (ref "R66") (pin "1") (pinfunction "1_1") (pintype "passive"))
    )
    (net (code "29") (name "/D7") (class "Default")
      (node (ref "ATMEGA2560") (pin "16") (pinfunction "PH4(OC4B)_16") (pintype "bidirectional"))
      (node (ref "R57") (pin "1") (pinfunction "1_1") (pintype "passive"))
      (node (ref "R67") (pin "1") (pinfunction "1_1") (pintype "passive"))
    )
    (net (code "30") (name "/D8") (class "Default")
      (node (ref "ATMEGA2560") (pin "17") (pinfunction "PH5(OC4C)_17") (pintype "bidirectional"))
      (node (ref "R58") (pin "1") (pinfunction "1_1") (pintype "passive"))
      (node (ref "R68") (pin "1") (pinfunction "1_1") (pintype "passive"))
    )
    (net (code "31") (name "/D9") (class "Default")
      (node (ref "ATMEGA2560") (pin "18") (pinfunction "PH6(OC2B)_18") (pintype "bidirectional"))
      (node (ref "R59") (pin "1") (pinfunction "1_1") (pintype "passive"))
      (node (ref "R69") (pin "1") (pinfunction "1_1") (pintype "passive"))
    )
    (net (code "32") (name "/D10") (class "Default")
      (node (ref "ATMEGA2560") (pin "23") (pinfunction "(OC2A/PCINT4)PB4_23") (pintype "bidirectional"))
      (node (ref "J1") (pin "1") (pinfunction "1_1") (pintype "passive"))
    )
    (net (code "33") (name "/D11") (class "Default")
      (node (ref "ATMEGA2560") (pin "24") (pinfunction "(OC1A/PCINT5)PB5_24") (pintype "bidirectional"))
      (node (ref "R51") (pin "1") (pinfunction "1_1") (pintype "passive"))
      (node (ref "R61") (pin "1") (pinfunction "1_1") (pintype "passive"))
    )
    (net (code "34") (name "/D12") (class "Default")
      (node (ref "ATMEGA2560") (pin "25") (pinfunction "(OC1B/PCINT6)PB6_25") (pintype "bidirectional"))
      (node (ref "R52") (pin "1") (pinfunction "1_1") (pintype "passive"))
      (node (ref "R62") (pin "1") (pinfunction "1_1") (pintype "passive"))
    )
    (net (code "35") (name "/D13(LED)") (class "Default")
      (node (ref "ATMEGA2560") (pin "26") (pinfunction "(OC0A/OC1C/PCINT7)PB7_26") (pintype "bidirectional"))
      (node (ref "RN3") (pin "8") (pinfunction "2_8") (pintype "passive"))
    )
    (net (code "36") (name "/D14") (class "Default")
      (node (ref "ATMEGA2560") (pin "64") (pinfunction "PJ1(TXD3/PCINT10)_64") (pintype "bidirectional"))
      (node (ref "U$2") (pin "CFG-3") (pinfunction "CFG-3_CFG-3") (pintype "bidirectional"))
    )
    (net (code "37") (name "/D15") (class "Default")
      (node (ref "ATMEGA2560") (pin "63") (pinfunction "PJ0(RXD3/PCINT9)_63") (pintype "bidirectional"))
      (node (ref "R32") (pin "2") (pinfunction "2_2") (pintype "passive"))
      (node (ref "U$2") (pin "CFG-6") (pinfunction "CFG-6_CFG-6") (pintype "bidirectional"))
    )
    (net (code "38") (name "/D16") (class "Default")
      (node (ref "ATMEGA2560") (pin "13") (pinfunction "PH1(TXD2)_13") (pintype "bidirectional"))
      (node (ref "AUX-4") (pin "21") (pinfunction "21_21") (pintype "passive"))
    )
    (net (code "39") (name "/D17") (class "Default")
      (node (ref "ATMEGA2560") (pin "12") (pinfunction "PH0(RXD2)_12") (pintype "bidirectional"))
      (node (ref "AUX-4") (pin "19") (pinfunction "19_19") (pintype "passive"))
    )
    (net (code "40") (name "/D18") (class "Default")
      (node (ref "ATMEGA2560") (pin "46") (pinfunction "(TXD1/INT3)PD3_46") (pintype "bidirectional"))
      (node (ref "U$4") (pin "IREF") (pinfunction "IREF_IREF") (pintype "bidirectional"))
      (node (ref "X-") (pin "1") (pinfunction "1_1") (pintype "passive"))
    )
    (net (code "41") (name "/D19") (class "Default")
      (node (ref "ATMEGA2560") (pin "45") (pinfunction "(RXD1/INT2)PD2_45") (pintype "bidirectional"))
      (node (ref "X+") (pin "1") (pinfunction "1_1") (pintype "passive"))
    )
    (net (code "42") (name "/D22") (class "Default")
      (node (ref "ATMEGA2560") (pin "78") (pinfunction "(AD0)PA0_78") (pintype "bidirectional"))
      (node (ref "U$5") (pin "STEP") (pinfunction "STEP_STEP") (pintype "input"))
    )
    (net (code "43") (name "/D23") (class "Default")
      (node (ref "ATMEGA2560") (pin "77") (pinfunction "(AD1)PA1_77") (pintype "bidirectional"))
      (node (ref "U$5") (pin "CFG-3") (pinfunction "CFG-3_CFG-3") (pintype "bidirectional"))
    )
    (net (code "44") (name "/D24") (class "Default")
      (node (ref "ATMEGA2560") (pin "76") (pinfunction "(AD2)PA2_76") (pintype "bidirectional"))
      (node (ref "R34") (pin "2") (pinfunction "2_2") (pintype "passive"))
      (node (ref "U$5") (pin "CFG-6") (pinfunction "CFG-6_CFG-6") (pintype "bidirectional"))
    )
    (net (code "45") (name "/D25") (class "Default")
      (node (ref "ATMEGA2560") (pin "75") (pinfunction "(AD3)PA3_75") (pintype "bidirectional"))
      (node (ref "U$3") (pin "DIR") (pinfunction "DIR_DIR") (pintype "input"))
    )
    (net (code "46") (name "/D26") (class "Default")
      (node (ref "ATMEGA2560") (pin "74") (pinfunction "(AD4)PA4_74") (pintype "bidirectional"))
      (node (ref "U$3") (pin "STEP") (pinfunction "STEP_STEP") (pintype "input"))
    )
    (net (code "47") (name "/D27") (class "Default")
      (node (ref "ATMEGA2560") (pin "73") (pinfunction "(AD5)PA5_73") (pintype "bidirectional"))
      (node (ref "U$3") (pin "CFG-3") (pinfunction "CFG-3_CFG-3") (pintype "bidirectional"))
    )
    (net (code "48") (name "/D28") (class "Default")
      (node (ref "ATMEGA2560") (pin "72") (pinfunction "(AD6)PA6_72") (pintype "bidirectional"))
      (node (ref "R33") (pin "2") (pinfunction "2_2") (pintype "passive"))
      (node (ref "U$3") (pin "CFG-6") (pinfunction "CFG-6_CFG-6") (pintype "bidirectional"))
    )
    (net (code "49") (name "/D29") (class "Default")
      (node (ref "ATMEGA2560") (pin "71") (pinfunction "(AD7)PA7_71") (pintype "bidirectional"))
      (node (ref "U$2") (pin "DIR") (pinfunction "DIR_DIR") (pintype "input"))
    )
    (net (code "50") (name "/D30") (class "Default")
      (node (ref "ATMEGA2560") (pin "60") (pinfunction "(A15)PC7_60") (pintype "bidirectional"))
      (node (ref "R31") (pin "2") (pinfunction "2_2") (pintype "passive"))
      (node (ref "U$1") (pin "CFG-6") (pinfunction "CFG-6_CFG-6") (pintype "bidirectional"))
    )
    (net (code "51") (name "/D31") (class "Default")
      (node (ref "ATMEGA2560") (pin "59") (pinfunction "(A14)PC6_59") (pintype "bidirectional"))
      (node (ref "U$1") (pin "CFG-3") (pinfunction "CFG-3_CFG-3") (pintype "bidirectional"))
    )
    (net (code "52") (name "/D32") (class "Default")
      (node (ref "ATMEGA2560") (pin "58") (pinfunction "(A13)PC5_58") (pintype "bidirectional"))
      (node (ref "U$1") (pin "STEP") (pinfunction "STEP_STEP") (pintype "input"))
    )
    (net (code "53") (name "/D33") (class "Default")
      (node (ref "ATMEGA2560") (pin "57") (pinfunction "(A12)PC4_57") (pintype "bidirectional"))
      (node (ref "U$1") (pin "DIR") (pinfunction "DIR_DIR") (pintype "input"))
    )
    (net (code "54") (name "/D34") (class "Default")
      (node (ref "ATMEGA2560") (pin "56") (pinfunction "(A11)PC3_56") (pintype "bidirectional"))
      (node (ref "AUX-4") (pin "5") (pinfunction "5_5") (pintype "passive"))
    )
    (net (code "55") (name "/D35") (class "Default")
      (node (ref "ATMEGA2560") (pin "55") (pinfunction "(A10)PC2_55") (pintype "bidirectional"))
      (node (ref "AUX-4") (pin "7") (pinfunction "7_7") (pintype "passive"))
    )
    (net (code "56") (name "/D36") (class "Default")
      (node (ref "ATMEGA2560") (pin "54") (pinfunction "(A9)PC1_54") (pintype "bidirectional"))
      (node (ref "AUX-4") (pin "9") (pinfunction "9_9") (pintype "passive"))
    )
    (net (code "57") (name "/D37") (class "Default")
      (node (ref "ATMEGA2560") (pin "53") (pinfunction "(A8)PC0_53") (pintype "bidirectional"))
      (node (ref "AUX-4") (pin "11") (pinfunction "11_11") (pintype "passive"))
    )
    (net (code "58") (name "/D38") (class "Default")
      (node (ref "ATMEGA2560") (pin "50") (pinfunction "(T0)PD7_50") (pintype "bidirectional"))
      (node (ref "AUX-4") (pin "17") (pinfunction "17_17") (pintype "passive"))
    )
    (net (code "59") (name "/D39") (class "Default")
      (node (ref "ATMEGA2560") (pin "70") (pinfunction "(ALE)PG2_70") (pintype "bidirectional"))
      (node (ref "U$2") (pin "STEP") (pinfunction "STEP_STEP") (pintype "input"))
    )
    (net (code "60") (name "/D40") (class "Default")
      (node (ref "ATMEGA2560") (pin "52") (pinfunction "(RD)PG1_52") (pintype "bidirectional"))
      (node (ref "AUX-4") (pin "13") (pinfunction "13_13") (pintype "passive"))
    )
    (net (code "61") (name "/D41") (class "Default")
      (node (ref "ATMEGA2560") (pin "51") (pinfunction "(WR)PG0_51") (pintype "bidirectional"))
      (node (ref "AUX-4") (pin "15") (pinfunction "15_15") (pintype "passive"))
    )
    (net (code "62") (name "/D42") (class "Default")
      (node (ref "ATMEGA2560") (pin "42") (pinfunction "PL7_42") (pintype "bidirectional"))
      (node (ref "U$5") (pin "IREF") (pinfunction "IREF_IREF") (pintype "bidirectional"))
      (node (ref "Y-") (pin "1") (pinfunction "1_1") (pintype "passive"))
    )
    (net (code "63") (name "/D43") (class "Default")
      (node (ref "ATMEGA2560") (pin "41") (pinfunction "PL6_41") (pintype "bidirectional"))
      (node (ref "Y+") (pin "1") (pinfunction "1_1") (pintype "passive"))
    )
    (net (code "64") (name "/D44") (class "Default")
      (node (ref "ATMEGA2560") (pin "40") (pinfunction "PL5(OC5C)_40") (pintype "bidirectional"))
      (node (ref "AUX-4") (pin "22") (pinfunction "22_22") (pintype "passive"))
    )
    (net (code "65") (name "/D45") (class "Default")
      (node (ref "ATMEGA2560") (pin "39") (pinfunction "PL4(OC5B)_39") (pintype "bidirectional"))
      (node (ref "AUX-4") (pin "20") (pinfunction "20_20") (pintype "passive"))
    )
    (net (code "66") (name "/D46") (class "Default")
      (node (ref "ATMEGA2560") (pin "38") (pinfunction "PL3(OC5A)_38") (pintype "bidirectional"))
      (node (ref "AUX-4") (pin "18") (pinfunction "18_18") (pintype "passive"))
    )
    (net (code "67") (name "/D47") (class "Default")
      (node (ref "ATMEGA2560") (pin "37") (pinfunction "PL2(T5)_37") (pintype "bidirectional"))
      (node (ref "U$3") (pin "IREF") (pinfunction "IREF_IREF") (pintype "bidirectional"))
      (node (ref "Z-") (pin "1") (pinfunction "1_1") (pintype "passive"))
    )
    (net (code "68") (name "/D48") (class "Default")
      (node (ref "ATMEGA2560") (pin "36") (pinfunction "PL1(ICP5)_36") (pintype "bidirectional"))
      (node (ref "R22") (pin "1") (pinfunction "1_1") (pintype "passive"))
    )
    (net (code "69") (name "/D49") (class "Default")
      (node (ref "ATMEGA2560") (pin "35") (pinfunction "PL0(ICP4)_35") (pintype "bidirectional"))
      (node (ref "Z+") (pin "1") (pinfunction "1_1") (pintype "passive"))
    )
    (net (code "70") (name "/D53") (class "Default")
      (node (ref "ATMEGA2560") (pin "19") (pinfunction "(SS/PCINT0)PB0_19") (pintype "bidirectional"))
      (node (ref "PS-ON") (pin "1") (pinfunction "1_1") (pintype "passive"))
    )
    (net (code "71") (name "/DTR") (class "Default")
      (node (ref "C7") (pin "1") (pinfunction "1_1") (pintype "passive"))
      (node (ref "IC4") (pin "13") (pinfunction "(CTS/HWB/AIN6/TO/INT7)PD7_13") (pintype "bidirectional"))
      (node (ref "RN4") (pin "4") (pinfunction "1_4") (pintype "passive"))
    )
    (net (code "72") (name "/M8RXD") (class "Default")
      (node (ref "IC4") (pin "9") (pinfunction "(TXD1/INT3)PD3_9") (pintype "bidirectional"))
      (node (ref "RN4") (pin "7") (pinfunction "2_7") (pintype "passive"))
    )
    (net (code "73") (name "/M8TXD") (class "Default")
      (node (ref "IC4") (pin "8") (pinfunction "(RXD1/AIN1/INT2)PD2_8") (pintype "bidirectional"))
      (node (ref "RN4") (pin "8") (pinfunction "2_8") (pintype "passive"))
    )
    (net (code "74") (name "/MISO") (class "Default")
      (node (ref "ATMEGA2560") (pin "22") (pinfunction "(MISO/PCINT3)PB3_22") (pintype "bidirectional"))
      (node (ref "ICSP") (pin "1") (pinfunction "1_1") (pintype "passive"))
      (node (ref "U$1") (pin "CFG-0") (pinfunction "CFG-0_CFG-0") (pintype "bidirectional"))
      (node (ref "U$2") (pin "CFG-0") (pinfunction "CFG-0_CFG-0") (pintype "bidirectional"))
      (node (ref "U$3") (pin "CFG-0") (pinfunction "CFG-0_CFG-0") (pintype "bidirectional"))
      (node (ref "U$4") (pin "CFG-0") (pinfunction "CFG-0_CFG-0") (pintype "bidirectional"))
      (node (ref "U$5") (pin "CFG-0") (pinfunction "CFG-0_CFG-0") (pintype "bidirectional"))
    )
    (net (code "75") (name "/MISO2") (class "Default")
      (node (ref "IC4") (pin "17") (pinfunction "(PD0/MISO/PCINT3)PB3_17") (pintype "bidirectional"))
      (node (ref "ICSP1") (pin "1") (pinfunction "1_1") (pintype "passive"))
    )
    (net (code "76") (name "/MOSI") (class "Default")
      (node (ref "ATMEGA2560") (pin "21") (pinfunction "(MOSI/PCINT2)PB2_21") (pintype "bidirectional"))
      (node (ref "ICSP") (pin "4") (pinfunction "4_4") (pintype "passive"))
      (node (ref "U$1") (pin "CFG-1") (pinfunction "CFG-1_CFG-1") (pintype "bidirectional"))
      (node (ref "U$2") (pin "CFG-1") (pinfunction "CFG-1_CFG-1") (pintype "bidirectional"))
      (node (ref "U$3") (pin "CFG-1") (pinfunction "CFG-1_CFG-1") (pintype "bidirectional"))
      (node (ref "U$4") (pin "CFG-1") (pinfunction "CFG-1_CFG-1") (pintype "bidirectional"))
      (node (ref "U$5") (pin "CFG-1") (pinfunction "CFG-1_CFG-1") (pintype "bidirectional"))
    )
    (net (code "77") (name "/MOSI2") (class "Default")
      (node (ref "IC4") (pin "16") (pinfunction "(PDI/MOSI/PCINT2)PB2_16") (pintype "bidirectional"))
      (node (ref "ICSP1") (pin "4") (pinfunction "4_4") (pintype "passive"))
    )
    (net (code "78") (name "/RD+") (class "Default")
      (node (ref "IC4") (pin "29") (pinfunction "D+_29") (pintype "bidirectional"))
      (node (ref "R6") (pin "1") (pinfunction "1_1") (pintype "passive"))
    )
    (net (code "79") (name "/RD-") (class "Default")
      (node (ref "IC4") (pin "30") (pinfunction "D-_30") (pintype "bidirectional"))
      (node (ref "R5") (pin "1") (pinfunction "1_1") (pintype "passive"))
    )
    (net (code "80") (name "/RESET") (class "Default")
      (node (ref "ATMEGA2560") (pin "30") (pinfunction "RESET_30") (pintype "input"))
      (node (ref "C1") (pin "1") (pinfunction "1_1") (pintype "passive"))
      (node (ref "C7") (pin "2") (pinfunction "2_2") (pintype "passive"))
      (node (ref "D3") (pin "A") (pinfunction "A_A") (pintype "passive"))
      (node (ref "ICSP") (pin "5") (pinfunction "5_5") (pintype "passive"))
      (node (ref "R4") (pin "1") (pinfunction "1_1") (pintype "passive"))
      (node (ref "RESET") (pin "1") (pinfunction "P_1") (pintype "passive"))
    )
    (net (code "81") (name "/RESET2") (class "Default")
      (node (ref "D2") (pin "A") (pinfunction "A_A") (pintype "passive"))
      (node (ref "IC4") (pin "24") (pinfunction "RESET(PC1/DW)_24") (pintype "input"))
      (node (ref "ICSP1") (pin "5") (pinfunction "5_5") (pintype "passive"))
      (node (ref "R3") (pin "1") (pinfunction "1_1") (pintype "passive"))
    )
    (net (code "82") (name "/RXL") (class "Default")
      (node (ref "IC4") (pin "10") (pinfunction "(INT5/AIN3)PD4_10") (pintype "bidirectional"))
      (node (ref "RX") (pin "C") (pinfunction "C_C") (pintype "passive"))
    )
    (net (code "83") (name "/SCK") (class "Default")
      (node (ref "ATMEGA2560") (pin "20") (pinfunction "(SCK/PCINT1)PB1_20") (pintype "bidirectional"))
      (node (ref "ICSP") (pin "3") (pinfunction "3_3") (pintype "passive"))
      (node (ref "U$1") (pin "CFG-2") (pinfunction "CFG-2_CFG-2") (pintype "bidirectional"))
      (node (ref "U$2") (pin "CFG-2") (pinfunction "CFG-2_CFG-2") (pintype "bidirectional"))
      (node (ref "U$3") (pin "CFG-2") (pinfunction "CFG-2_CFG-2") (pintype "bidirectional"))
      (node (ref "U$4") (pin "CFG-2") (pinfunction "CFG-2_CFG-2") (pintype "bidirectional"))
      (node (ref "U$5") (pin "CFG-2") (pinfunction "CFG-2_CFG-2") (pintype "bidirectional"))
    )
    (net (code "84") (name "/SCK2") (class "Default")
      (node (ref "IC4") (pin "15") (pinfunction "(SCLK/PCINT1)PB1_15") (pintype "bidirectional"))
      (node (ref "ICSP1") (pin "3") (pinfunction "3_3") (pintype "passive"))
    )
    (net (code "85") (name "/SCL") (class "Default")
      (node (ref "ATMEGA2560") (pin "43") (pinfunction "(SCL/INT0)PD0_43") (pintype "bidirectional"))
      (node (ref "I2C") (pin "4") (pinfunction "4_4") (pintype "passive"))
      (node (ref "R12") (pin "1") (pinfunction "1_1") (pintype "passive"))
    )
    (net (code "86") (name "/SDA") (class "Default")
      (node (ref "ATMEGA2560") (pin "44") (pinfunction "(SDA/INT1)PD1_44") (pintype "bidirectional"))
      (node (ref "I2C") (pin "3") (pinfunction "3_3") (pintype "passive"))
      (node (ref "R11") (pin "1") (pinfunction "1_1") (pintype "passive"))
    )
    (net (code "87") (name "/TXL") (class "Default")
      (node (ref "IC4") (pin "11") (pinfunction "(XCK/AIN4/PCINT12)PD5_11") (pintype "bidirectional"))
      (node (ref "TX") (pin "C") (pinfunction "C_C") (pintype "passive"))
    )
    (net (code "88") (name "/UGND") (class "Default")
      (node (ref "C10") (pin "2") (pinfunction "2_2") (pintype "passive"))
      (node (ref "GND") (pin "1") (pinfunction "1_1") (pintype "passive"))
      (node (ref "IC4") (pin "28") (pinfunction "UGND_28") (pintype "power_in"))
      (node (ref "L1") (pin "1") (pinfunction "1_1") (pintype "passive"))
      (node (ref "X2") (pin "4") (pinfunction "4_4") (pintype "bidirectional"))
    )
    (net (code "89") (name "/USBVCC") (class "Default")
      (node (ref "C8") (pin "1") (pinfunction "1_1") (pintype "passive"))
      (node (ref "IC4") (pin "31") (pinfunction "UVCC_31") (pintype "power_in"))
      (node (ref "X2") (pin "1") (pinfunction "1_1") (pintype "bidirectional"))
    )
    (net (code "90") (name "/USHIELD") (class "Default")
      (node (ref "L1") (pin "2") (pinfunction "2_2") (pintype "passive"))
      (node (ref "X2") (pin "P$1") (pinfunction "P$1_P$1") (pintype "bidirectional"))
      (node (ref "X2") (pin "P$2") (pinfunction "P$2_P$2") (pintype "bidirectional"))
      (node (ref "Z1") (pin "1") (pinfunction "1_1") (pintype "passive"))
      (node (ref "Z2") (pin "1") (pinfunction "1_1") (pintype "passive"))
    )
    (net (code "91") (name "/VIN") (class "Default")
      (node (ref "C2") (pin "1") (pinfunction "1_1") (pintype "passive"))
      (node (ref "D4") (pin "C") (pinfunction "C_C") (pintype "passive"))
      (node (ref "IC1") (pin "3") (pinfunction "IN_3") (pintype "input"))
      (node (ref "PC1") (pin "+") (pinfunction "+_+") (pintype "passive"))
    )
    (net (code "92") (name "/VUCAP") (class "Default")
      (node (ref "C10") (pin "1") (pinfunction "1_1") (pintype "passive"))
      (node (ref "IC4") (pin "27") (pinfunction "UCAP_27") (pintype "passive"))
    )
    (net (code "93") (name "/XT1") (class "Default")
      (node (ref "C14") (pin "1") (pinfunction "1_1") (pintype "passive"))
      (node (ref "IC4") (pin "1") (pinfunction "XTAL1_1") (pintype "bidirectional"))
      (node (ref "R2") (pin "1") (pinfunction "1_1") (pintype "passive"))
      (node (ref "Y2") (pin "2") (pinfunction "2_2") (pintype "passive"))
    )
    (net (code "94") (name "/XT2") (class "Default")
      (node (ref "C15") (pin "1") (pinfunction "1_1") (pintype "passive"))
      (node (ref "IC4") (pin "2") (pinfunction "XTAL2(PC0)_2") (pintype "bidirectional"))
      (node (ref "R2") (pin "2") (pinfunction "2_2") (pintype "passive"))
      (node (ref "Y2") (pin "1") (pinfunction "1_1") (pintype "passive"))
    )
    (net (code "95") (name "/XTAL1") (class "Default")
      (node (ref "ATMEGA2560") (pin "34") (pinfunction "XTAL1_34") (pintype "input"))
      (node (ref "R1") (pin "1") (pinfunction "1_1") (pintype "passive"))
      (node (ref "Y1") (pin "3") (pinfunction "3_3") (pintype "passive"))
    )
    (net (code "96") (name "/XTAL2") (class "Default")
      (node (ref "ATMEGA2560") (pin "33") (pinfunction "XTAL2_33") (pintype "output"))
      (node (ref "R1") (pin "2") (pinfunction "2_2") (pintype "passive"))
      (node (ref "Y1") (pin "1") (pinfunction "1_1") (pintype "passive"))
    )
    (net (code "97") (name "GND") (class "Default")
      (node (ref "A-OUT") (pin "2") (pinfunction "2_2") (pintype "passive"))
      (node (ref "ATMEGA2560") (pin "11") (pinfunction "GND_11") (pintype "power_in"))
      (node (ref "ATMEGA2560") (pin "32") (pinfunction "GND1_32") (pintype "power_in"))
      (node (ref "ATMEGA2560") (pin "62") (pinfunction "GND2_62") (pintype "power_in"))
      (node (ref "ATMEGA2560") (pin "81") (pinfunction "GND3_81") (pintype "power_in"))
      (node (ref "ATMEGA2560") (pin "99") (pinfunction "AGND_99") (pintype "power_in"))
      (node (ref "AUX-4") (pin "23") (pinfunction "23_23") (pintype "passive"))
      (node (ref "AUX-4") (pin "24") (pinfunction "24_24") (pintype "passive"))
      (node (ref "AUX-4") (pin "3") (pinfunction "3_3") (pintype "passive"))
      (node (ref "AUX-4") (pin "4") (pinfunction "4_4") (pintype "passive"))
      (node (ref "C1") (pin "2") (pinfunction "2_2") (pintype "passive"))
      (node (ref "C11") (pin "2") (pinfunction "2_2") (pintype "passive"))
      (node (ref "C12") (pin "-") (pinfunction "-_-") (pintype "passive"))
      (node (ref "C13") (pin "2") (pinfunction "2_2") (pintype "passive"))
      (node (ref "C14") (pin "2") (pinfunction "2_2") (pintype "passive"))
      (node (ref "C15") (pin "2") (pinfunction "2_2") (pintype "passive"))
      (node (ref "C2") (pin "2") (pinfunction "2_2") (pintype "passive"))
      (node (ref "C20") (pin "2") (pinfunction "2_2") (pintype "passive"))
      (node (ref "C21") (pin "-") (pinfunction "-_-") (pintype "passive"))
      (node (ref "C22") (pin "-") (pinfunction "-_-") (pintype "passive"))
      (node (ref "C23") (pin "-") (pinfunction "-_-") (pintype "passive"))
      (node (ref "C24") (pin "-") (pinfunction "-_-") (pintype "passive"))
      (node (ref "C25") (pin "-") (pinfunction "-_-") (pintype "passive"))
      (node (ref "C4") (pin "2") (pinfunction "2_2") (pintype "passive"))
      (node (ref "C40") (pin "-") (pinfunction "-_-") (pintype "passive"))
      (node (ref "C41") (pin "-") (pinfunction "-_-") (pintype "passive"))
      (node (ref "C42") (pin "-") (pinfunction "-_-") (pintype "passive"))
      (node (ref "C43") (pin "-") (pinfunction "-_-") (pintype "passive"))
      (node (ref "C5") (pin "2") (pinfunction "2_2") (pintype "passive"))
      (node (ref "C6") (pin "2") (pinfunction "2_2") (pintype "passive"))
      (node (ref "C8") (pin "2") (pinfunction "2_2") (pintype "passive"))
      (node (ref "C9") (pin "2") (pinfunction "2_2") (pintype "passive"))
      (node (ref "D5") (pin "A") (pinfunction "A_A") (pintype "passive"))
      (node (ref "GND") (pin "2") (pinfunction "2_2") (pintype "passive"))
      (node (ref "I2C") (pin "2") (pinfunction "2_2") (pintype "passive"))
      (node (ref "IC1") (pin "1") (pinfunction "GND/ADJ_1") (pintype "input"))
      (node (ref "IC4") (pin "3") (pinfunction "GND_3") (pintype "power_in"))
      (node (ref "IC4") (pin "33") (pinfunction "PAD_33") (pintype "power_in"))
      (node (ref "ICSP") (pin "6") (pinfunction "6_6") (pintype "passive"))
      (node (ref "ICSP1") (pin "6") (pinfunction "6_6") (pintype "passive"))
      (node (ref "J1") (pin "2") (pinfunction "2_2") (pintype "passive"))
      (node (ref "J2") (pin "1") (pinfunction "1_1") (pintype "passive"))
      (node (ref "J3") (pin "1") (pinfunction "1_1") (pintype "passive"))
      (node (ref "J4") (pin "1") (pinfunction "1_1") (pintype "passive"))
      (node (ref "J5") (pin "1") (pinfunction "1_1") (pintype "passive"))
      (node (ref "JP7") (pin "1") (pinfunction "1_1") (pintype "passive"))
      (node (ref "JP7") (pin "3") (pinfunction "3_3") (pintype "passive"))
      (node (ref "JP7") (pin "5") (pinfunction "5_5") (pintype "passive"))
      (node (ref "JP7") (pin "7") (pinfunction "7_7") (pintype "passive"))
      (node (ref "L") (pin "C") (pinfunction "C_C") (pintype "passive"))
      (node (ref "ON") (pin "C") (pinfunction "C_C") (pintype "passive"))
      (node (ref "P1") (pin "3") (pinfunction "CW_3") (pintype "bidirectional"))
      (node (ref "PC1") (pin "-") (pinfunction "-_-") (pintype "passive"))
      (node (ref "PC2") (pin "-") (pinfunction "-_-") (pintype "passive"))
      (node (ref "Q1") (pin "S") (pinfunction "S_S") (pintype "passive"))
      (node (ref "Q2") (pin "S") (pinfunction "S_S") (pintype "passive"))
      (node (ref "Q3") (pin "1") (pinfunction "S_1") (pintype "passive"))
      (node (ref "Q3") (pin "3") (pinfunction "S_3") (pintype "passive"))
      (node (ref "Q4") (pin "1") (pinfunction "S_1") (pintype "passive"))
      (node (ref "Q4") (pin "3") (pinfunction "S_3") (pintype "passive"))
      (node (ref "R21") (pin "1") (pinfunction "1_1") (pintype "passive"))
      (node (ref "R61") (pin "2") (pinfunction "2_2") (pintype "passive"))
      (node (ref "R62") (pin "2") (pinfunction "2_2") (pintype "passive"))
      (node (ref "R66") (pin "2") (pinfunction "2_2") (pintype "passive"))
      (node (ref "R67") (pin "2") (pinfunction "2_2") (pintype "passive"))
      (node (ref "R68") (pin "2") (pinfunction "2_2") (pintype "passive"))
      (node (ref "R69") (pin "2") (pinfunction "2_2") (pintype "passive"))
      (node (ref "RESET") (pin "2") (pinfunction "S_2") (pintype "passive"))
      (node (ref "RN4") (pin "5") (pinfunction "2_5") (pintype "passive"))
      (node (ref "SERIAL") (pin "2") (pinfunction "2_2") (pintype "passive"))
      (node (ref "U$1") (pin "GND") (pinfunction "GND_GND") (pintype "power_in"))
      (node (ref "U$1") (pin "GND@0") (pinfunction "GND_GND@0") (pintype "power_in"))
      (node (ref "U$2") (pin "GND") (pinfunction "GND_GND") (pintype "power_in"))
      (node (ref "U$2") (pin "GND@0") (pinfunction "GND_GND@0") (pintype "power_in"))
      (node (ref "U$3") (pin "GND") (pinfunction "GND_GND") (pintype "power_in"))
      (node (ref "U$3") (pin "GND@0") (pinfunction "GND_GND@0") (pintype "power_in"))
      (node (ref "U$4") (pin "GND") (pinfunction "GND_GND") (pintype "power_in"))
      (node (ref "U$4") (pin "GND@0") (pinfunction "GND_GND@0") (pintype "power_in"))
      (node (ref "U$5") (pin "GND") (pinfunction "GND_GND") (pintype "power_in"))
      (node (ref "U$5") (pin "GND@0") (pinfunction "GND_GND@0") (pintype "power_in"))
      (node (ref "X+") (pin "2") (pinfunction "2_2") (pintype "passive"))
      (node (ref "X-") (pin "2") (pinfunction "2_2") (pintype "passive"))
      (node (ref "X1") (pin "2") (pinfunction "1_2") (pintype "passive"))
      (node (ref "Y+") (pin "2") (pinfunction "2_2") (pintype "passive"))
      (node (ref "Y-") (pin "2") (pinfunction "2_2") (pintype "passive"))
      (node (ref "Y1") (pin "2") (pinfunction "2_2") (pintype "passive"))
      (node (ref "Z+") (pin "2") (pinfunction "2_2") (pintype "passive"))
      (node (ref "Z-") (pin "2") (pinfunction "2_2") (pintype "passive"))
      (node (ref "Z12V") (pin "2") (pinfunction "2_2") (pintype "passive"))
    )
    (net (code "98") (name "Net-(C20-Pad1)") (class "Default")
      (node (ref "C20") (pin "1") (pinfunction "1_1") (pintype "passive"))
      (node (ref "R21") (pin "2") (pinfunction "2_2") (pintype "passive"))
      (node (ref "R22") (pin "2") (pinfunction "2_2") (pintype "passive"))
      (node (ref "Z12V") (pin "1") (pinfunction "1_1") (pintype "passive"))
    )
    (net (code "99") (name "Net-(F1-Pad2)") (class "Default")
      (node (ref "F1") (pin "2") (pinfunction "2_2") (pintype "passive"))
      (node (ref "X1") (pin "1") (pinfunction "1_1") (pintype "passive"))
    )
    (net (code "100") (name "Net-(FANS-Pad2)") (class "Default")
      (node (ref "FANS") (pin "2") (pinfunction "2_2") (pintype "passive"))
      (node (ref "L6") (pin "C") (pinfunction "C_C") (pintype "passive"))
      (node (ref "Q3") (pin "5") (pinfunction "D_5") (pintype "passive"))
      (node (ref "Q3") (pin "6") (pinfunction "D_6") (pintype "passive"))
    )
    (net (code "101") (name "Net-(FANS-Pad4)") (class "Default")
      (node (ref "FANS") (pin "4") (pinfunction "4_4") (pintype "passive"))
      (node (ref "L7") (pin "C") (pinfunction "C_C") (pintype "passive"))
      (node (ref "Q3") (pin "7") (pinfunction "D_7") (pintype "passive"))
      (node (ref "Q3") (pin "8") (pinfunction "D_8") (pintype "passive"))
    )
    (net (code "102") (name "Net-(FANS-Pad6)") (class "Default")
      (node (ref "FANS") (pin "6") (pinfunction "6_6") (pintype "passive"))
      (node (ref "L8") (pin "C") (pinfunction "C_C") (pintype "passive"))
      (node (ref "Q4") (pin "5") (pinfunction "D_5") (pintype "passive"))
      (node (ref "Q4") (pin "6") (pinfunction "D_6") (pintype "passive"))
    )
    (net (code "103") (name "Net-(FANS-Pad8)") (class "Default")
      (node (ref "FANS") (pin "8") (pinfunction "8_8") (pintype "passive"))
      (node (ref "L9") (pin "C") (pinfunction "C_C") (pintype "passive"))
      (node (ref "Q4") (pin "7") (pinfunction "D_7") (pintype "passive"))
      (node (ref "Q4") (pin "8") (pinfunction "D_8") (pintype "passive"))
    )
    (net (code "104") (name "Net-(L-PadA)") (class "Default")
      (node (ref "L") (pin "A") (pinfunction "A_A") (pintype "passive"))
      (node (ref "RN3") (pin "1") (pinfunction "1_1") (pintype "passive"))
    )
    (net (code "105") (name "Net-(L6-PadA)") (class "Default")
      (node (ref "L6") (pin "A") (pinfunction "A_A") (pintype "passive"))
      (node (ref "R76") (pin "1") (pinfunction "1_1") (pintype "passive"))
    )
    (net (code "106") (name "Net-(L7-PadA)") (class "Default")
      (node (ref "L7") (pin "A") (pinfunction "A_A") (pintype "passive"))
      (node (ref "R77") (pin "1") (pinfunction "1_1") (pintype "passive"))
    )
    (net (code "107") (name "Net-(L8-PadA)") (class "Default")
      (node (ref "L8") (pin "A") (pinfunction "A_A") (pintype "passive"))
      (node (ref "R78") (pin "1") (pinfunction "1_1") (pintype "passive"))
    )
    (net (code "108") (name "Net-(L9-PadA)") (class "Default")
      (node (ref "L9") (pin "A") (pinfunction "A_A") (pintype "passive"))
      (node (ref "R79") (pin "1") (pinfunction "1_1") (pintype "passive"))
    )
    (net (code "109") (name "Net-(L11-PadA)") (class "Default")
      (node (ref "L11") (pin "A") (pinfunction "A_A") (pintype "passive"))
      (node (ref "R71") (pin "2") (pinfunction "2_2") (pintype "passive"))
    )
    (net (code "110") (name "Net-(L11-PadC)") (class "Default")
      (node (ref "L11") (pin "C") (pinfunction "C_C") (pintype "passive"))
      (node (ref "Q1") (pin "D") (pinfunction "D_D") (pintype "passive"))
      (node (ref "X3") (pin "1") (pinfunction "1_1") (pintype "passive"))
    )
    (net (code "111") (name "Net-(L12-PadA)") (class "Default")
      (node (ref "L12") (pin "A") (pinfunction "A_A") (pintype "passive"))
      (node (ref "R72") (pin "2") (pinfunction "2_2") (pintype "passive"))
    )
    (net (code "112") (name "Net-(Q1-PadG)") (class "Default")
      (node (ref "Q1") (pin "G") (pinfunction "G_G") (pintype "passive"))
      (node (ref "R51") (pin "2") (pinfunction "2_2") (pintype "passive"))
    )
    (net (code "113") (name "Net-(Q2-PadG)") (class "Default")
      (node (ref "Q2") (pin "G") (pinfunction "G_G") (pintype "passive"))
      (node (ref "R52") (pin "2") (pinfunction "2_2") (pintype "passive"))
    )
    (net (code "114") (name "Net-(Q3A-G)") (class "Default")
      (node (ref "Q3") (pin "2") (pinfunction "G_2") (pintype "passive"))
      (node (ref "R57") (pin "2") (pinfunction "2_2") (pintype "passive"))
    )
    (net (code "115") (name "Net-(Q3B-G)") (class "Default")
      (node (ref "Q3") (pin "4") (pinfunction "G_4") (pintype "passive"))
      (node (ref "R56") (pin "2") (pinfunction "2_2") (pintype "passive"))
    )
    (net (code "116") (name "Net-(Q4A-G)") (class "Default")
      (node (ref "Q4") (pin "2") (pinfunction "G_2") (pintype "passive"))
      (node (ref "R59") (pin "2") (pinfunction "2_2") (pintype "passive"))
    )
    (net (code "117") (name "Net-(Q4B-G)") (class "Default")
      (node (ref "Q4") (pin "4") (pinfunction "G_4") (pintype "passive"))
      (node (ref "R58") (pin "2") (pinfunction "2_2") (pintype "passive"))
    )
    (net (code "118") (name "Net-(RN3B-2)") (class "Default")
      (node (ref "ON") (pin "A") (pinfunction "A_A") (pintype "passive"))
      (node (ref "RN3") (pin "7") (pinfunction "2_7") (pintype "passive"))
    )
    (net (code "119") (name "Net-(RN3C-2)") (class "Default")
      (node (ref "RN3") (pin "6") (pinfunction "2_6") (pintype "passive"))
      (node (ref "RX") (pin "A") (pinfunction "A_A") (pintype "passive"))
    )
    (net (code "120") (name "Net-(RN3D-2)") (class "Default")
      (node (ref "RN3") (pin "5") (pinfunction "2_5") (pintype "passive"))
      (node (ref "TX") (pin "A") (pinfunction "A_A") (pintype "passive"))
    )
    (net (code "121") (name "Net-(U$1-O1A)") (class "Default")
      (node (ref "U$1") (pin "OA1") (pinfunction "O1A_OA1") (pintype "output"))
      (node (ref "X-MOT") (pin "3") (pinfunction "3_3") (pintype "passive"))
    )
    (net (code "122") (name "Net-(U$1-O1B)") (class "Default")
      (node (ref "U$1") (pin "OA2") (pinfunction "O1B_OA2") (pintype "output"))
      (node (ref "X-MOT") (pin "4") (pinfunction "4_4") (pintype "passive"))
    )
    (net (code "123") (name "Net-(U$1-O2A)") (class "Default")
      (node (ref "U$1") (pin "OB1") (pinfunction "O2A_OB1") (pintype "output"))
      (node (ref "X-MOT") (pin "2") (pinfunction "2_2") (pintype "passive"))
    )
    (net (code "124") (name "Net-(U$1-O2B)") (class "Default")
      (node (ref "U$1") (pin "OB2") (pinfunction "O2B_OB2") (pintype "output"))
      (node (ref "X-MOT") (pin "1") (pinfunction "1_1") (pintype "passive"))
    )
    (net (code "125") (name "Net-(U$2-O1A)") (class "Default")
      (node (ref "U$2") (pin "OA1") (pinfunction "O1A_OA1") (pintype "output"))
      (node (ref "Y-MOT") (pin "3") (pinfunction "3_3") (pintype "passive"))
    )
    (net (code "126") (name "Net-(U$2-O1B)") (class "Default")
      (node (ref "U$2") (pin "OA2") (pinfunction "O1B_OA2") (pintype "output"))
      (node (ref "Y-MOT") (pin "4") (pinfunction "4_4") (pintype "passive"))
    )
    (net (code "127") (name "Net-(U$2-O2A)") (class "Default")
      (node (ref "U$2") (pin "OB1") (pinfunction "O2A_OB1") (pintype "output"))
      (node (ref "Y-MOT") (pin "2") (pinfunction "2_2") (pintype "passive"))
    )
    (net (code "128") (name "Net-(U$2-O2B)") (class "Default")
      (node (ref "U$2") (pin "OB2") (pinfunction "O2B_OB2") (pintype "output"))
      (node (ref "Y-MOT") (pin "1") (pinfunction "1_1") (pintype "passive"))
    )
    (net (code "129") (name "Net-(U$3-O1A)") (class "Default")
      (node (ref "U$3") (pin "OA1") (pinfunction "O1A_OA1") (pintype "output"))
      (node (ref "Z-MOT") (pin "3") (pinfunction "3_3") (pintype "passive"))
      (node (ref "Z-MOT1") (pin "3") (pinfunction "3_3") (pintype "passive"))
    )
    (net (code "130") (name "Net-(U$3-O1B)") (class "Default")
      (node (ref "U$3") (pin "OA2") (pinfunction "O1B_OA2") (pintype "output"))
      (node (ref "Z-MOT") (pin "4") (pinfunction "4_4") (pintype "passive"))
      (node (ref "Z-MOT1") (pin "4") (pinfunction "4_4") (pintype "passive"))
    )
    (net (code "131") (name "Net-(U$3-O2A)") (class "Default")
      (node (ref "U$3") (pin "OB1") (pinfunction "O2A_OB1") (pintype "output"))
      (node (ref "Z-MOT") (pin "2") (pinfunction "2_2") (pintype "passive"))
      (node (ref "Z-MOT1") (pin "2") (pinfunction "2_2") (pintype "passive"))
    )
    (net (code "132") (name "Net-(U$3-O2B)") (class "Default")
      (node (ref "U$3") (pin "OB2") (pinfunction "O2B_OB2") (pintype "output"))
      (node (ref "Z-MOT") (pin "1") (pinfunction "1_1") (pintype "passive"))
      (node (ref "Z-MOT1") (pin "1") (pinfunction "1_1") (pintype "passive"))
    )
    (net (code "133") (name "Net-(U$4-O1A)") (class "Default")
      (node (ref "E1-MOT") (pin "3") (pinfunction "3_3") (pintype "passive"))
      (node (ref "U$4") (pin "OA1") (pinfunction "O1A_OA1") (pintype "output"))
    )
    (net (code "134") (name "Net-(U$4-O1B)") (class "Default")
      (node (ref "E1-MOT") (pin "4") (pinfunction "4_4") (pintype "passive"))
      (node (ref "U$4") (pin "OA2") (pinfunction "O1B_OA2") (pintype "output"))
    )
    (net (code "135") (name "Net-(U$4-O2A)") (class "Default")
      (node (ref "E1-MOT") (pin "2") (pinfunction "2_2") (pintype "passive"))
      (node (ref "U$4") (pin "OB1") (pinfunction "O2A_OB1") (pintype "output"))
    )
    (net (code "136") (name "Net-(U$4-O2B)") (class "Default")
      (node (ref "E1-MOT") (pin "1") (pinfunction "1_1") (pintype "passive"))
      (node (ref "U$4") (pin "OB2") (pinfunction "O2B_OB2") (pintype "output"))
    )
    (net (code "137") (name "Net-(U$5-O1A)") (class "Default")
      (node (ref "E0-MOT") (pin "3") (pinfunction "3_3") (pintype "passive"))
      (node (ref "U$5") (pin "OA1") (pinfunction "O1A_OA1") (pintype "output"))
    )
    (net (code "138") (name "Net-(U$5-O1B)") (class "Default")
      (node (ref "E0-MOT") (pin "4") (pinfunction "4_4") (pintype "passive"))
      (node (ref "U$5") (pin "OA2") (pinfunction "O1B_OA2") (pintype "output"))
    )
    (net (code "139") (name "Net-(U$5-O2A)") (class "Default")
      (node (ref "E0-MOT") (pin "2") (pinfunction "2_2") (pintype "passive"))
      (node (ref "U$5") (pin "OB1") (pinfunction "O2A_OB1") (pintype "output"))
    )
    (net (code "140") (name "Net-(U$5-O2B)") (class "Default")
      (node (ref "E0-MOT") (pin "1") (pinfunction "1_1") (pintype "passive"))
      (node (ref "U$5") (pin "OB2") (pinfunction "O2B_OB2") (pintype "output"))
    )
    (net (code "141") (name "Net-(X3C-1)") (class "Default")
      (node (ref "L12") (pin "C") (pinfunction "C_C") (pintype "passive"))
      (node (ref "Q2") (pin "D") (pinfunction "D_D") (pintype "passive"))
      (node (ref "X3") (pin "3") (pinfunction "1_3") (pintype "passive"))
    )
    (net (code "142") (name "unconnected-(ATMEGA2560-(CLKO{slash}ICP3{slash}INT7)PE7-Pad9)") (class "Default")
      (node (ref "ATMEGA2560") (pin "9") (pinfunction "(CLKO/ICP3/INT7)PE7_9") (pintype "bidirectional"))
    )
    (net (code "143") (name "unconnected-(ATMEGA2560-(ICP1)PD4-Pad47)") (class "Default")
      (node (ref "ATMEGA2560") (pin "47") (pinfunction "(ICP1)PD4_47") (pintype "bidirectional"))
    )
    (net (code "144") (name "unconnected-(ATMEGA2560-(T1)PD6-Pad49)") (class "Default")
      (node (ref "ATMEGA2560") (pin "49") (pinfunction "(T1)PD6_49") (pintype "bidirectional"))
    )
    (net (code "145") (name "unconnected-(ATMEGA2560-(T3{slash}INT6)PE6-Pad8)") (class "Default")
      (node (ref "ATMEGA2560") (pin "8") (pinfunction "(T3/INT6)PE6_8") (pintype "bidirectional"))
    )
    (net (code "146") (name "unconnected-(ATMEGA2560-(TOSC1)PG4-Pad29)") (class "Default")
      (node (ref "ATMEGA2560") (pin "29") (pinfunction "(TOSC1)PG4_29") (pintype "bidirectional"))
    )
    (net (code "147") (name "unconnected-(ATMEGA2560-(TOSC2)PG3-Pad28)") (class "Default")
      (node (ref "ATMEGA2560") (pin "28") (pinfunction "(TOSC2)PG3_28") (pintype "bidirectional"))
    )
    (net (code "148") (name "unconnected-(ATMEGA2560-(XCK0{slash}AIN0)PE2-Pad4)") (class "Default")
      (node (ref "ATMEGA2560") (pin "4") (pinfunction "(XCK0/AIN0)PE2_4") (pintype "bidirectional"))
    )
    (net (code "149") (name "unconnected-(ATMEGA2560-(XCK1)PD5-Pad48)") (class "Default")
      (node (ref "ATMEGA2560") (pin "48") (pinfunction "(XCK1)PD5_48") (pintype "bidirectional"))
    )
    (net (code "150") (name "unconnected-(ATMEGA2560-AREF-Pad98)") (class "Default")
      (node (ref "ATMEGA2560") (pin "98") (pinfunction "AREF_98") (pintype "bidirectional"))
    )
    (net (code "151") (name "unconnected-(ATMEGA2560-PH2(XCK2)-Pad14)") (class "Default")
      (node (ref "ATMEGA2560") (pin "14") (pinfunction "PH2(XCK2)_14") (pintype "bidirectional"))
    )
    (net (code "152") (name "unconnected-(ATMEGA2560-PH7(T4)-Pad27)") (class "Default")
      (node (ref "ATMEGA2560") (pin "27") (pinfunction "PH7(T4)_27") (pintype "bidirectional"))
    )
    (net (code "153") (name "unconnected-(ATMEGA2560-PJ2(XCK3{slash}PCINT11)-Pad65)") (class "Default")
      (node (ref "ATMEGA2560") (pin "65") (pinfunction "PJ2(XCK3/PCINT11)_65") (pintype "bidirectional"))
    )
    (net (code "154") (name "unconnected-(ATMEGA2560-PJ3(PCINT12)-Pad66)") (class "Default")
      (node (ref "ATMEGA2560") (pin "66") (pinfunction "PJ3(PCINT12)_66") (pintype "bidirectional"))
    )
    (net (code "155") (name "unconnected-(ATMEGA2560-PJ4(PCINT13)-Pad67)") (class "Default")
      (node (ref "ATMEGA2560") (pin "67") (pinfunction "PJ4(PCINT13)_67") (pintype "bidirectional"))
    )
    (net (code "156") (name "unconnected-(ATMEGA2560-PJ5(PCINT14)-Pad68)") (class "Default")
      (node (ref "ATMEGA2560") (pin "68") (pinfunction "PJ5(PCINT14)_68") (pintype "bidirectional"))
    )
    (net (code "157") (name "unconnected-(ATMEGA2560-PJ6(PCINT15)-Pad69)") (class "Default")
      (node (ref "ATMEGA2560") (pin "69") (pinfunction "PJ6(PCINT15)_69") (pintype "bidirectional"))
    )
    (net (code "158") (name "unconnected-(ATMEGA2560-PJ7-Pad79)") (class "Default")
      (node (ref "ATMEGA2560") (pin "79") (pinfunction "PJ7_79") (pintype "bidirectional"))
    )
    (net (code "159") (name "unconnected-(IC4-(AIN0{slash}INT1)PD1-Pad7)") (class "Default")
      (node (ref "IC4") (pin "7") (pinfunction "(AIN0/INT1)PD1_7") (pintype "bidirectional"))
    )
    (net (code "160") (name "unconnected-(IC4-(AIN2{slash}PCINT11)PC2-Pad5)") (class "Default")
      (node (ref "IC4") (pin "5") (pinfunction "(AIN2/PCINT11)PC2_5") (pintype "bidirectional"))
    )
    (net (code "161") (name "unconnected-(IC4-(INT4{slash}ICP1{slash}CLK0)PC7-Pad22)") (class "Default")
      (node (ref "IC4") (pin "22") (pinfunction "(INT4/ICP1/CLK0)PC7_22") (pintype "bidirectional"))
    )
    (net (code "162") (name "unconnected-(IC4-(OC0B{slash}INT0)PD0-Pad6)") (class "Default")
      (node (ref "IC4") (pin "6") (pinfunction "(OC0B/INT0)PD0_6") (pintype "bidirectional"))
    )
    (net (code "163") (name "unconnected-(IC4-(OC1A{slash}PCINT8)PC6-Pad23)") (class "Default")
      (node (ref "IC4") (pin "23") (pinfunction "(OC1A/PCINT8)PC6_23") (pintype "bidirectional"))
    )
    (net (code "164") (name "unconnected-(IC4-(PCINT5)PB5-Pad19)") (class "Default")
      (node (ref "IC4") (pin "19") (pinfunction "(PCINT5)PB5_19") (pintype "bidirectional"))
    )
    (net (code "165") (name "unconnected-(IC4-(PCINT6)PB6-Pad20)") (class "Default")
      (node (ref "IC4") (pin "20") (pinfunction "(PCINT6)PB6_20") (pintype "bidirectional"))
    )
    (net (code "166") (name "unconnected-(IC4-(PCINT7{slash}OC0A{slash}OC1C)PB7-Pad21)") (class "Default")
      (node (ref "IC4") (pin "21") (pinfunction "(PCINT7/OC0A/OC1C)PB7_21") (pintype "bidirectional"))
    )
    (net (code "167") (name "unconnected-(IC4-(PCINT9{slash}OC1B)PC5-Pad25)") (class "Default")
      (node (ref "IC4") (pin "25") (pinfunction "(PCINT9/OC1B)PC5_25") (pintype "bidirectional"))
    )
    (net (code "168") (name "unconnected-(IC4-(PCINT10)PC4-Pad26)") (class "Default")
      (node (ref "IC4") (pin "26") (pinfunction "(PCINT10)PC4_26") (pintype "bidirectional"))
    )
    (net (code "169") (name "unconnected-(IC4-(RTS{slash}AIN5{slash}INT6)PD6-Pad12)") (class "Default")
      (node (ref "IC4") (pin "12") (pinfunction "(RTS/AIN5/INT6)PD6_12") (pintype "bidirectional"))
    )
    (net (code "170") (name "unconnected-(IC4-(SS{slash}PCINT0)PB0-Pad14)") (class "Default")
      (node (ref "IC4") (pin "14") (pinfunction "(SS/PCINT0)PB0_14") (pintype "bidirectional"))
    )
    (net (code "171") (name "unconnected-(IC4-(T1{slash}PCINT4)PB4-Pad18)") (class "Default")
      (node (ref "IC4") (pin "18") (pinfunction "(T1/PCINT4)PB4_18") (pintype "bidirectional"))
    )
    (net (code "172") (name "unconnected-(RN4C-1-Pad3)") (class "Default")
      (node (ref "RN4") (pin "3") (pinfunction "1_3") (pintype "passive"))
    )
    (net (code "173") (name "unconnected-(RN4C-2-Pad6)") (class "Default")
      (node (ref "RN4") (pin "6") (pinfunction "2_6") (pintype "passive"))
    )
    (net (code "174") (name "unconnected-(U$1-PadIREF)") (class "Default")
      (node (ref "U$1") (pin "IREF") (pinfunction "IREF_IREF") (pintype "bidirectional"))
    )
    (net (code "175") (name "unconnected-(U$2-PadIREF)") (class "Default")
      (node (ref "U$2") (pin "IREF") (pinfunction "IREF_IREF") (pintype "bidirectional"))
    )
  )
)
